# l8r.net
KiCad netlist of a schematic drawn in EAGLE
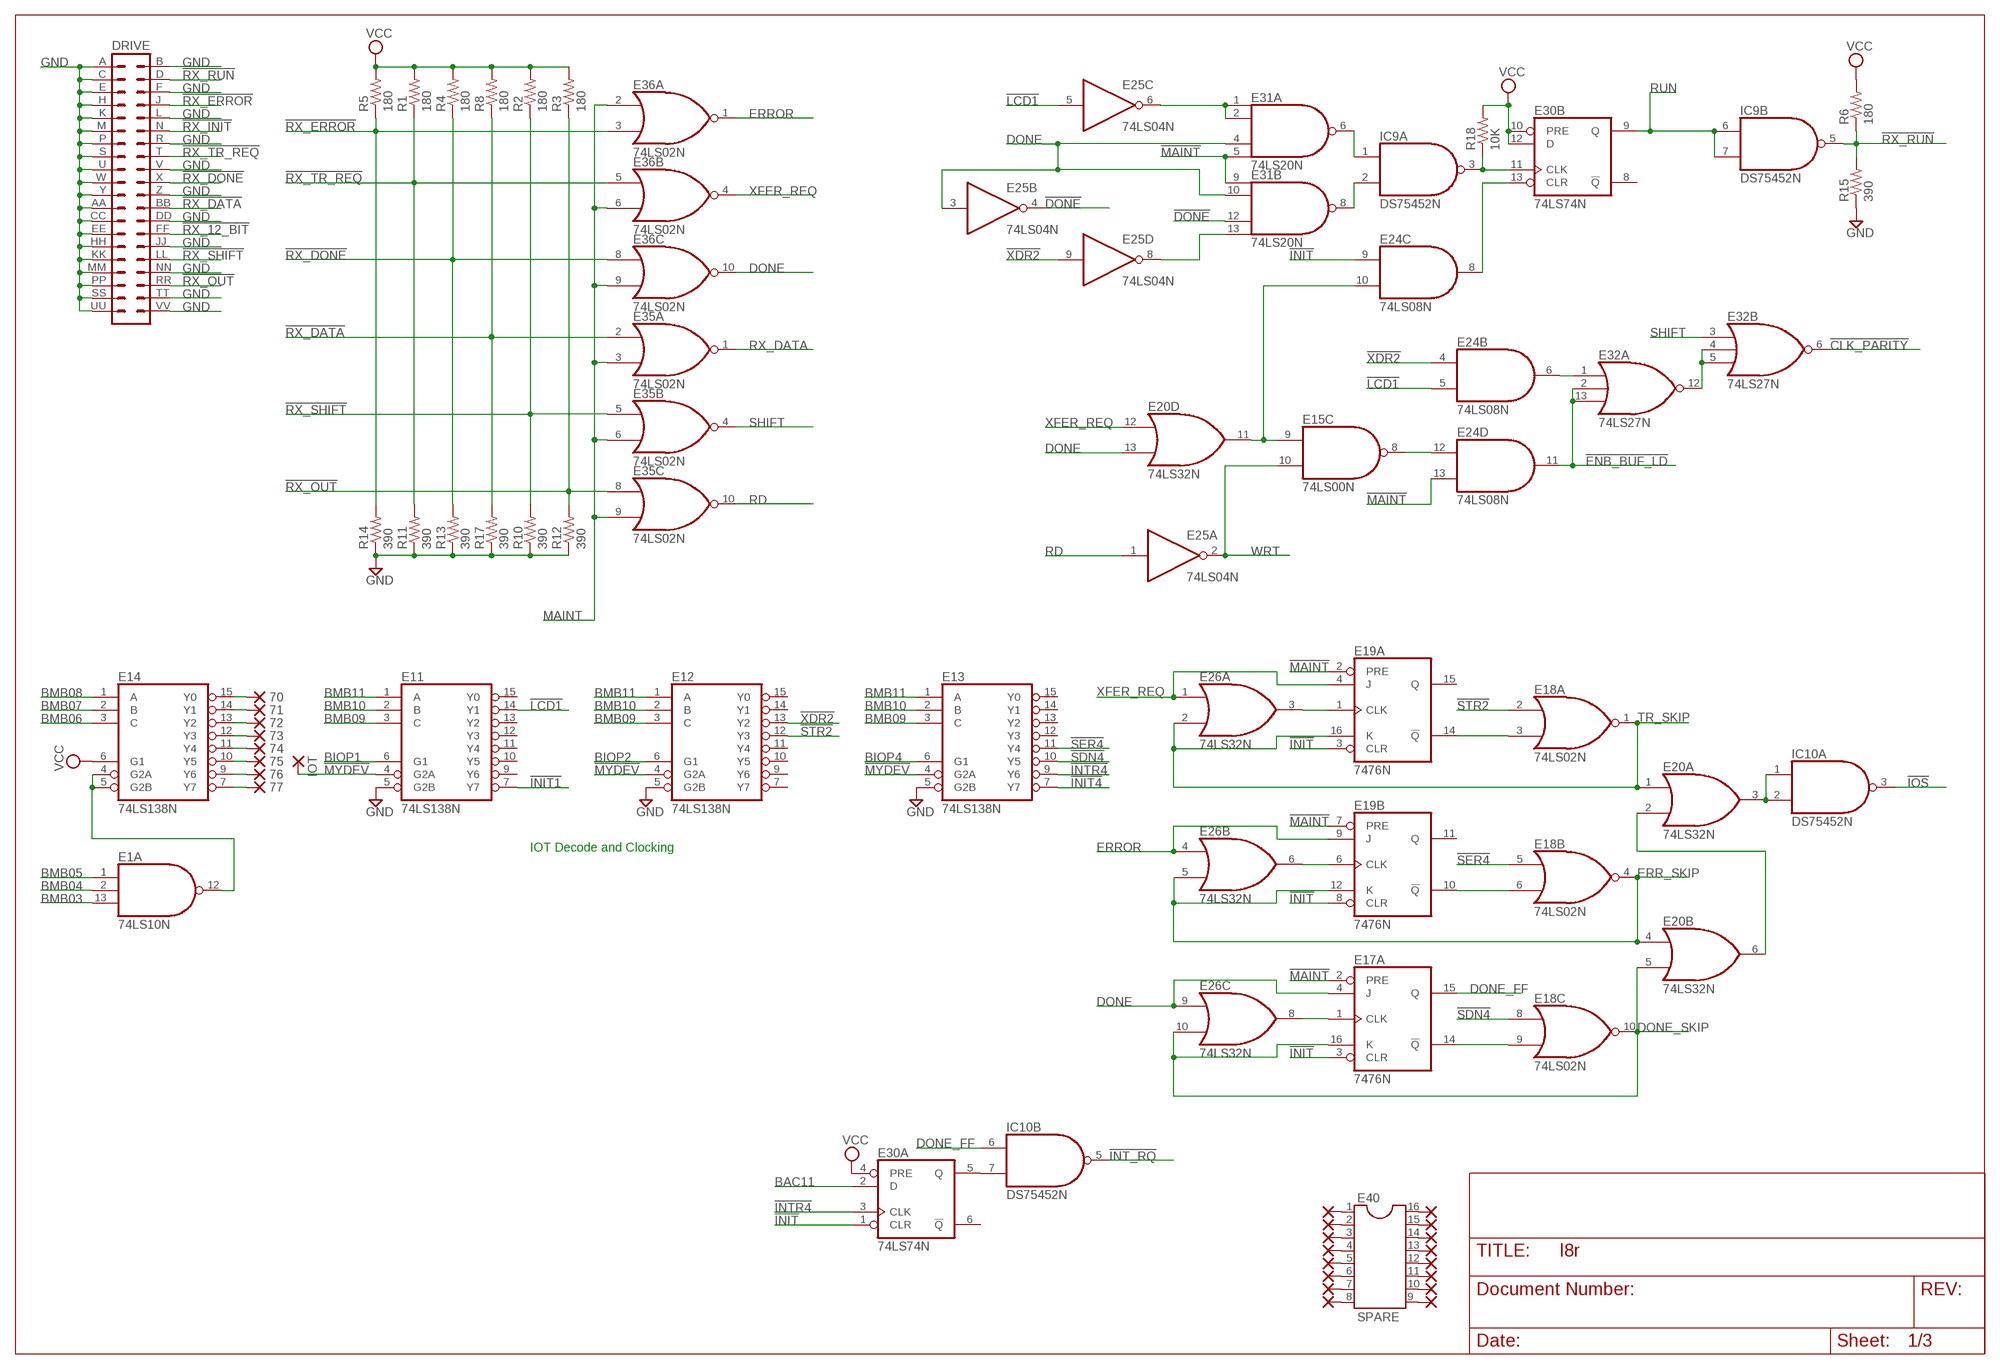
[diagram p0: schematic, sheet 1]
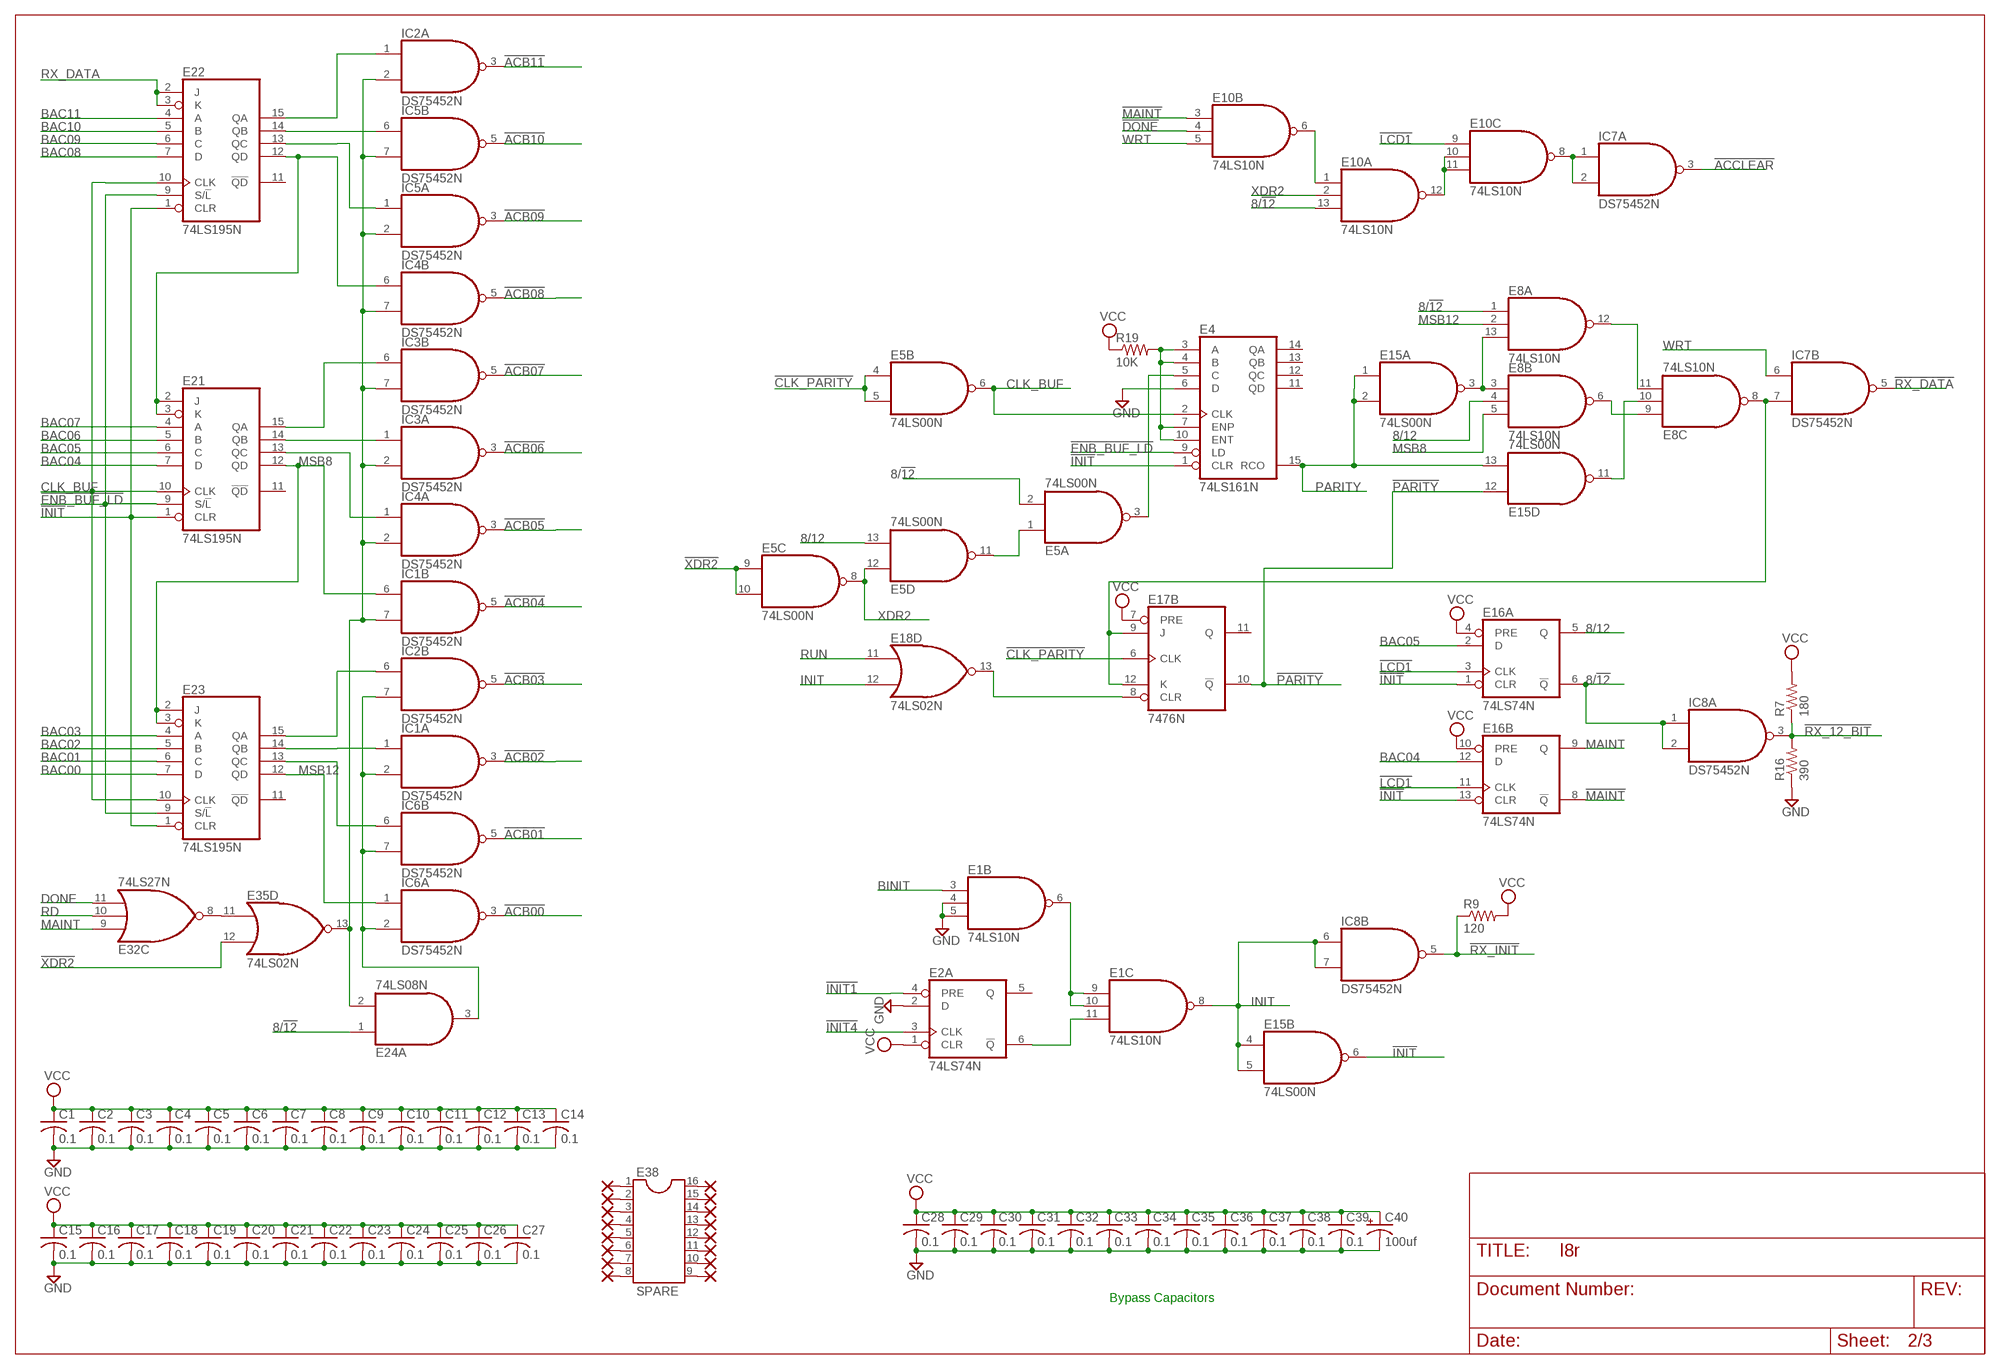
[diagram p1: schematic, sheet 2]
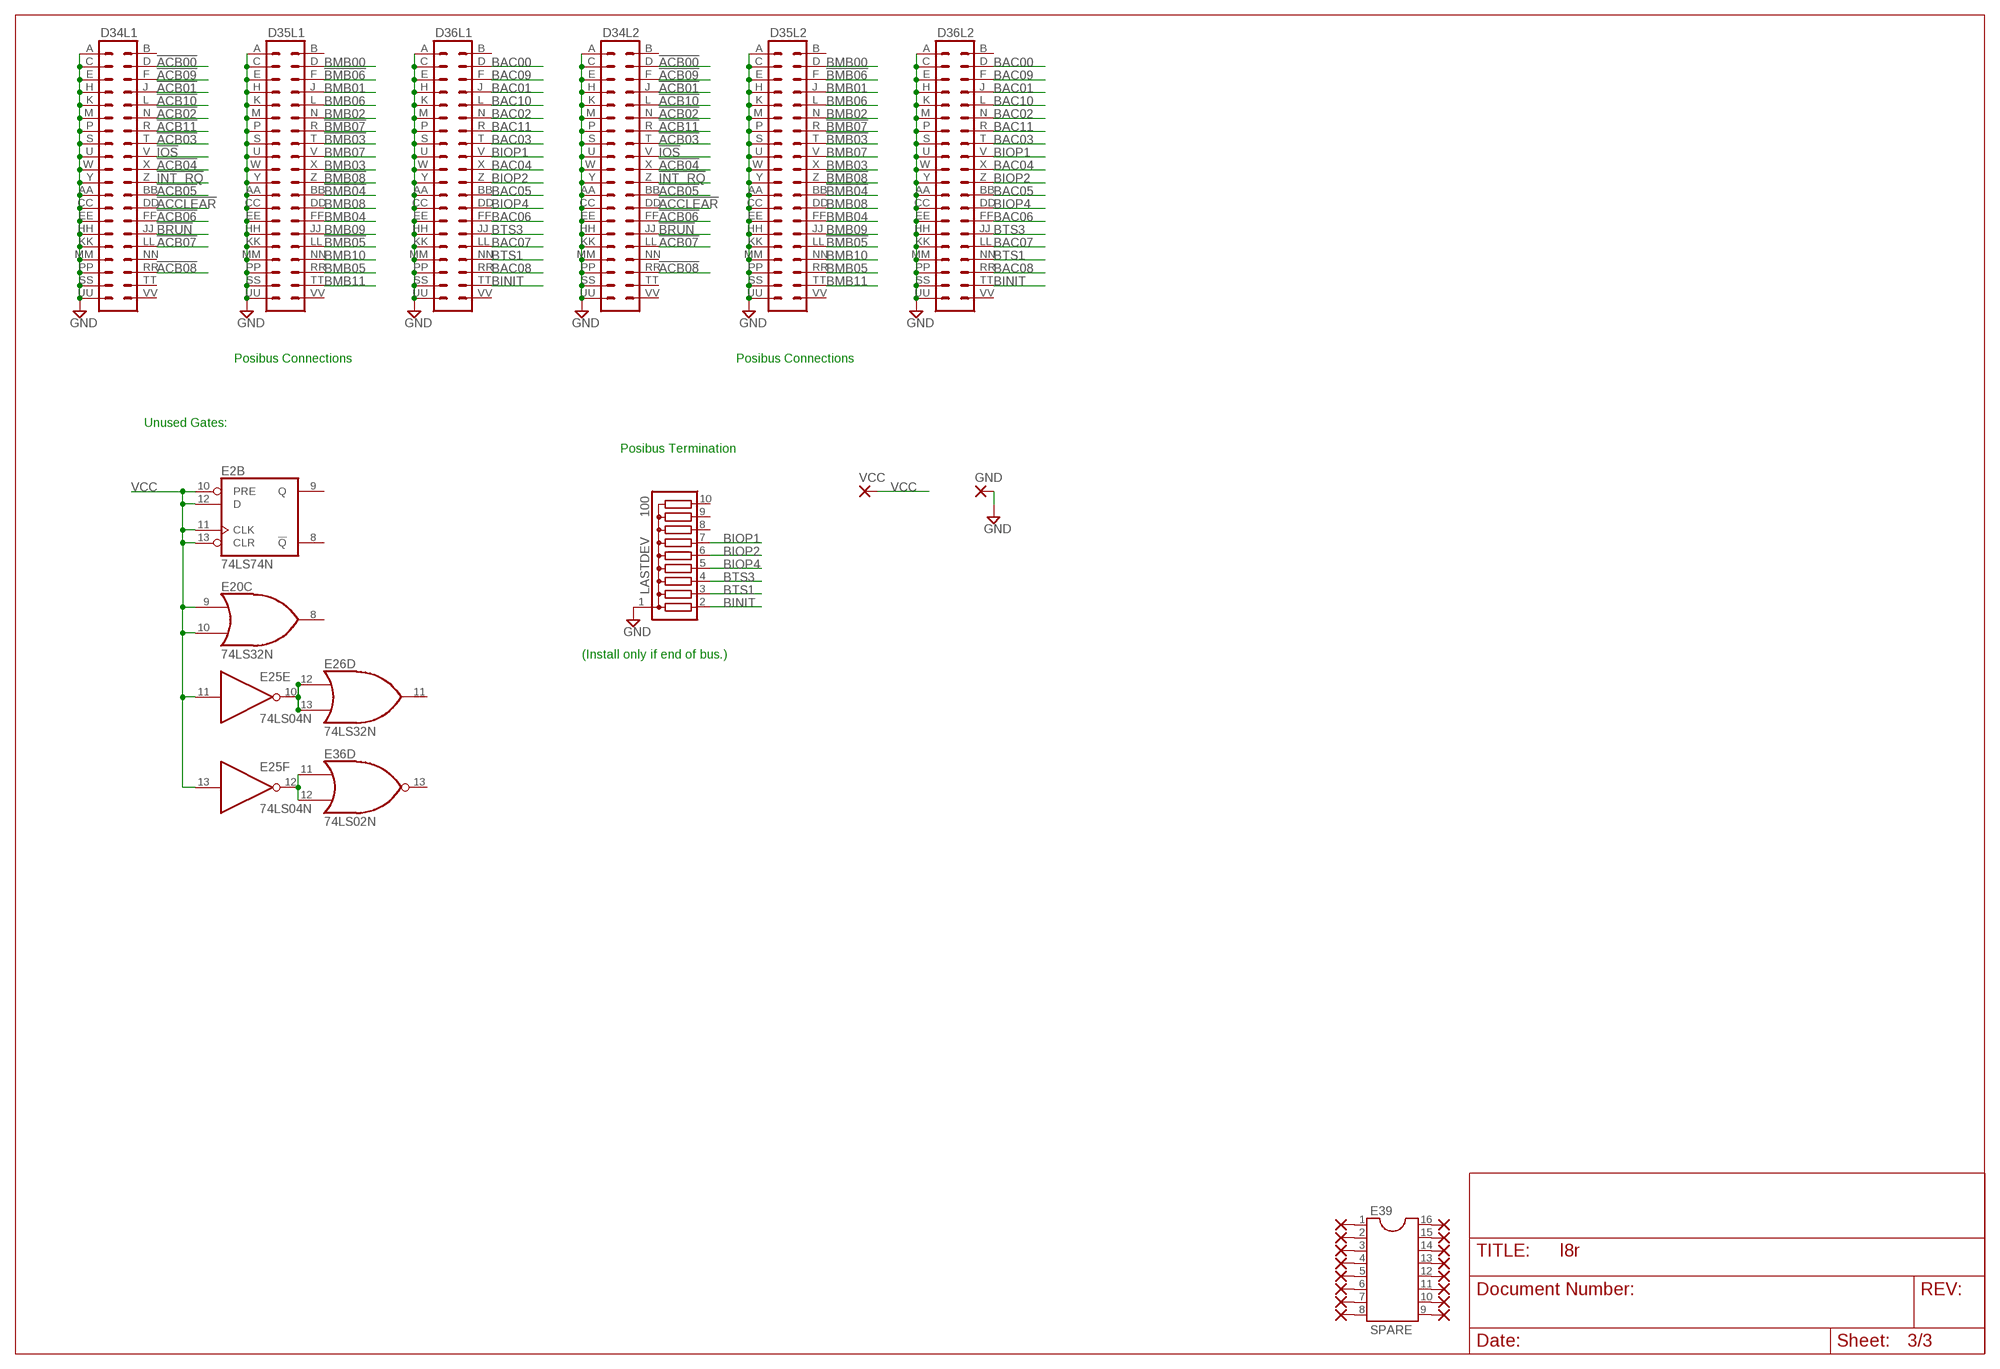
[diagram p2: schematic, sheet 3]

(export (version "E")
  (design (tool "Eeschema 10.0.6"))
  (components
    (comp (ref "D34L1")
      (value "DEC40PINV")
      (footprint "eagle-import:DEC40PINV")
      (libsource (lib "eagle-import") (part "DEC40PINV"))
    )
    (comp (ref "D34L2")
      (value "DEC40PINV")
      (footprint "eagle-import:DEC40PINV")
      (libsource (lib "eagle-import") (part "DEC40PINV"))
    )
    (comp (ref "D35L1")
      (value "DEC40PINV")
      (footprint "eagle-import:DEC40PINV")
      (libsource (lib "eagle-import") (part "DEC40PINV"))
    )
    (comp (ref "D35L2")
      (value "DEC40PINV")
      (footprint "eagle-import:DEC40PINV")
      (libsource (lib "eagle-import") (part "DEC40PINV"))
    )
    (comp (ref "D36L1")
      (value "DEC40PINV")
      (footprint "eagle-import:DEC40PINV")
      (libsource (lib "eagle-import") (part "DEC40PINV"))
    )
    (comp (ref "D36L2")
      (value "DEC40PINV")
      (footprint "eagle-import:DEC40PINV")
      (libsource (lib "eagle-import") (part "DEC40PINV"))
    )
    (comp (ref "E2")
      (value "74LS74N")
      (footprint "eagle-import:DIL14")
      (libsource (lib "eagle-import") (part "7474NLS"))
    )
    (comp (ref "E20")
      (value "74LS32N")
      (footprint "eagle-import:DIL14")
      (libsource (lib "eagle-import") (part "7432NLS"))
    )
    (comp (ref "E25")
      (value "74LS04N")
      (footprint "eagle-import:DIL14")
      (libsource (lib "eagle-import") (part "7404NLS"))
    )
    (comp (ref "E26")
      (value "74LS32N")
      (footprint "eagle-import:DIL14")
      (libsource (lib "eagle-import") (part "7432NLS"))
    )
    (comp (ref "E36")
      (value "74LS02N")
      (footprint "eagle-import:DIL14")
      (libsource (lib "eagle-import") (part "7402NLS"))
    )
    (comp (ref "E39")
      (value "SPARE")
      (footprint "eagle-import:DIL16")
      (libsource (lib "eagle-import") (part "DIL16"))
    )
    (comp (ref "GND")
      (value "2,54/0,8")
      (footprint "eagle-import:2,54_0,8")
      (libsource (lib "eagle-import") (part "2,54/0,8"))
    )
    (comp (ref "LASTDEV")
      (value "100")
      (footprint "eagle-import:SIL10")
      (libsource (lib "eagle-import") (part "G09R"))
    )
    (comp (ref "PAD42")
      (value "1,6/0,8")
      (footprint "eagle-import:1,6_0,8")
      (libsource (lib "eagle-import") (part "1,6/0,8"))
    )
    (comp (ref "PAD43")
      (value "1,6/0,8")
      (footprint "eagle-import:1,6_0,8")
      (libsource (lib "eagle-import") (part "1,6/0,8"))
    )
    (comp (ref "PAD44")
      (value "1,6/0,8")
      (footprint "eagle-import:1,6_0,8")
      (libsource (lib "eagle-import") (part "1,6/0,8"))
    )
    (comp (ref "PAD45")
      (value "1,6/0,8")
      (footprint "eagle-import:1,6_0,8")
      (libsource (lib "eagle-import") (part "1,6/0,8"))
    )
    (comp (ref "PAD46")
      (value "1,6/0,8")
      (footprint "eagle-import:1,6_0,8")
      (libsource (lib "eagle-import") (part "1,6/0,8"))
    )
    (comp (ref "PAD47")
      (value "1,6/0,8")
      (footprint "eagle-import:1,6_0,8")
      (libsource (lib "eagle-import") (part "1,6/0,8"))
    )
    (comp (ref "PAD48")
      (value "1,6/0,8")
      (footprint "eagle-import:1,6_0,8")
      (libsource (lib "eagle-import") (part "1,6/0,8"))
    )
    (comp (ref "PAD49")
      (value "1,6/0,8")
      (footprint "eagle-import:1,6_0,8")
      (libsource (lib "eagle-import") (part "1,6/0,8"))
    )
    (comp (ref "PAD50")
      (value "1,6/0,8")
      (footprint "eagle-import:1,6_0,8")
      (libsource (lib "eagle-import") (part "1,6/0,8"))
    )
    (comp (ref "PAD51")
      (value "1,6/0,8")
      (footprint "eagle-import:1,6_0,8")
      (libsource (lib "eagle-import") (part "1,6/0,8"))
    )
    (comp (ref "PAD52")
      (value "1,6/0,8")
      (footprint "eagle-import:1,6_0,8")
      (libsource (lib "eagle-import") (part "1,6/0,8"))
    )
    (comp (ref "PAD53")
      (value "1,6/0,8")
      (footprint "eagle-import:1,6_0,8")
      (libsource (lib "eagle-import") (part "1,6/0,8"))
    )
    (comp (ref "PAD54")
      (value "1,6/0,8")
      (footprint "eagle-import:1,6_0,8")
      (libsource (lib "eagle-import") (part "1,6/0,8"))
    )
    (comp (ref "PAD55")
      (value "1,6/0,8")
      (footprint "eagle-import:1,6_0,8")
      (libsource (lib "eagle-import") (part "1,6/0,8"))
    )
    (comp (ref "PAD56")
      (value "1,6/0,8")
      (footprint "eagle-import:1,6_0,8")
      (libsource (lib "eagle-import") (part "1,6/0,8"))
    )
    (comp (ref "PAD57")
      (value "1,6/0,8")
      (footprint "eagle-import:1,6_0,8")
      (libsource (lib "eagle-import") (part "1,6/0,8"))
    )
    (comp (ref "VCC")
      (value "2,54/0,8")
      (footprint "eagle-import:2,54_0,8")
      (libsource (lib "eagle-import") (part "2,54/0,8"))
    )
    (comp (ref "70")
      (value "1,6/0,8")
      (footprint "eagle-import:1,6_0,8")
      (libsource (lib "eagle-import") (part "1,6/0,8"))
    )
    (comp (ref "71")
      (value "1,6/0,8")
      (footprint "eagle-import:1,6_0,8")
      (libsource (lib "eagle-import") (part "1,6/0,8"))
    )
    (comp (ref "72")
      (value "1,6/0,8")
      (footprint "eagle-import:1,6_0,8")
      (libsource (lib "eagle-import") (part "1,6/0,8"))
    )
    (comp (ref "73")
      (value "1,6/0,8")
      (footprint "eagle-import:1,6_0,8")
      (libsource (lib "eagle-import") (part "1,6/0,8"))
    )
    (comp (ref "74")
      (value "1,6/0,8")
      (footprint "eagle-import:1,6_0,8")
      (libsource (lib "eagle-import") (part "1,6/0,8"))
    )
    (comp (ref "75")
      (value "1,6/0,8")
      (footprint "eagle-import:1,6_0,8")
      (libsource (lib "eagle-import") (part "1,6/0,8"))
    )
    (comp (ref "76")
      (value "1,6/0,8")
      (footprint "eagle-import:1,6_0,8")
      (libsource (lib "eagle-import") (part "1,6/0,8"))
    )
    (comp (ref "77")
      (value "1,6/0,8")
      (footprint "eagle-import:1,6_0,8")
      (libsource (lib "eagle-import") (part "1,6/0,8"))
    )
    (comp (ref "DRIVE")
      (value "DEC40PINV")
      (footprint "eagle-import:DEC40PINV")
      (libsource (lib "eagle-import") (part "DEC40PINV"))
    )
    (comp (ref "E1")
      (value "74LS10N")
      (footprint "eagle-import:DIL14")
      (libsource (lib "eagle-import") (part "7410NLS"))
    )
    (comp (ref "E11")
      (value "74LS138N")
      (footprint "eagle-import:DIL16")
      (libsource (lib "eagle-import") (part "74138NLS"))
    )
    (comp (ref "E12")
      (value "74LS138N")
      (footprint "eagle-import:DIL16")
      (libsource (lib "eagle-import") (part "74138NLS"))
    )
    (comp (ref "E13")
      (value "74LS138N")
      (footprint "eagle-import:DIL16")
      (libsource (lib "eagle-import") (part "74138NLS"))
    )
    (comp (ref "E14")
      (value "74LS138N")
      (footprint "eagle-import:DIL16")
      (libsource (lib "eagle-import") (part "74138NLS"))
    )
    (comp (ref "E15")
      (value "74LS00N")
      (footprint "eagle-import:DIL14")
      (libsource (lib "eagle-import") (part "7400NLS"))
    )
    (comp (ref "E17")
      (value "7476N")
      (footprint "eagle-import:DIL16")
      (libsource (lib "eagle-import") (part "7476N"))
    )
    (comp (ref "E18")
      (value "74LS02N")
      (footprint "eagle-import:DIL14")
      (libsource (lib "eagle-import") (part "7402NLS"))
    )
    (comp (ref "E19")
      (value "7476N")
      (footprint "eagle-import:DIL16")
      (libsource (lib "eagle-import") (part "7476N"))
    )
    (comp (ref "E24")
      (value "74LS08N")
      (footprint "eagle-import:DIL14")
      (libsource (lib "eagle-import") (part "7408NLS"))
    )
    (comp (ref "E30")
      (value "74LS74N")
      (footprint "eagle-import:DIL14")
      (libsource (lib "eagle-import") (part "7474NLS"))
    )
    (comp (ref "E31")
      (value "74LS20N")
      (footprint "eagle-import:DIL14")
      (libsource (lib "eagle-import") (part "7420NLS"))
    )
    (comp (ref "E32")
      (value "74LS27N")
      (footprint "eagle-import:DIL14")
      (libsource (lib "eagle-import") (part "7427NLS"))
    )
    (comp (ref "E35")
      (value "74LS02N")
      (footprint "eagle-import:DIL14")
      (libsource (lib "eagle-import") (part "7402NLS"))
    )
    (comp (ref "E40")
      (value "SPARE")
      (footprint "eagle-import:DIL16")
      (libsource (lib "eagle-import") (part "DIL16"))
    )
    (comp (ref "IC9")
      (value "DS75452N")
      (footprint "eagle-import:DIL08")
      (libsource (lib "eagle-import") (part "DS75452N"))
    )
    (comp (ref "IC10")
      (value "DS75452N")
      (footprint "eagle-import:DIL08")
      (libsource (lib "eagle-import") (part "DS75452N"))
    )
    (comp (ref "IOT")
      (value "1,6/0,8")
      (footprint "eagle-import:1,6_0,8")
      (libsource (lib "eagle-import") (part "1,6/0,8"))
    )
    (comp (ref "PAD18")
      (value "1,6/0,8")
      (footprint "eagle-import:1,6_0,8")
      (libsource (lib "eagle-import") (part "1,6/0,8"))
    )
    (comp (ref "PAD19")
      (value "1,6/0,8")
      (footprint "eagle-import:1,6_0,8")
      (libsource (lib "eagle-import") (part "1,6/0,8"))
    )
    (comp (ref "PAD28")
      (value "1,6/0,8")
      (footprint "eagle-import:1,6_0,8")
      (libsource (lib "eagle-import") (part "1,6/0,8"))
    )
    (comp (ref "PAD29")
      (value "1,6/0,8")
      (footprint "eagle-import:1,6_0,8")
      (libsource (lib "eagle-import") (part "1,6/0,8"))
    )
    (comp (ref "PAD30")
      (value "1,6/0,8")
      (footprint "eagle-import:1,6_0,8")
      (libsource (lib "eagle-import") (part "1,6/0,8"))
    )
    (comp (ref "PAD31")
      (value "1,6/0,8")
      (footprint "eagle-import:1,6_0,8")
      (libsource (lib "eagle-import") (part "1,6/0,8"))
    )
    (comp (ref "PAD32")
      (value "1,6/0,8")
      (footprint "eagle-import:1,6_0,8")
      (libsource (lib "eagle-import") (part "1,6/0,8"))
    )
    (comp (ref "PAD33")
      (value "1,6/0,8")
      (footprint "eagle-import:1,6_0,8")
      (libsource (lib "eagle-import") (part "1,6/0,8"))
    )
    (comp (ref "PAD34")
      (value "1,6/0,8")
      (footprint "eagle-import:1,6_0,8")
      (libsource (lib "eagle-import") (part "1,6/0,8"))
    )
    (comp (ref "PAD35")
      (value "1,6/0,8")
      (footprint "eagle-import:1,6_0,8")
      (libsource (lib "eagle-import") (part "1,6/0,8"))
    )
    (comp (ref "PAD36")
      (value "1,6/0,8")
      (footprint "eagle-import:1,6_0,8")
      (libsource (lib "eagle-import") (part "1,6/0,8"))
    )
    (comp (ref "PAD37")
      (value "1,6/0,8")
      (footprint "eagle-import:1,6_0,8")
      (libsource (lib "eagle-import") (part "1,6/0,8"))
    )
    (comp (ref "PAD38")
      (value "1,6/0,8")
      (footprint "eagle-import:1,6_0,8")
      (libsource (lib "eagle-import") (part "1,6/0,8"))
    )
    (comp (ref "PAD39")
      (value "1,6/0,8")
      (footprint "eagle-import:1,6_0,8")
      (libsource (lib "eagle-import") (part "1,6/0,8"))
    )
    (comp (ref "PAD40")
      (value "1,6/0,8")
      (footprint "eagle-import:1,6_0,8")
      (libsource (lib "eagle-import") (part "1,6/0,8"))
    )
    (comp (ref "PAD41")
      (value "1,6/0,8")
      (footprint "eagle-import:1,6_0,8")
      (libsource (lib "eagle-import") (part "1,6/0,8"))
    )
    (comp (ref "R1")
      (value "180")
      (footprint "eagle-import:0207_10")
      (libsource (lib "eagle-import") (part "R-US_0207/10"))
    )
    (comp (ref "R2")
      (value "180")
      (footprint "eagle-import:0207_10")
      (libsource (lib "eagle-import") (part "R-US_0207/10"))
    )
    (comp (ref "R3")
      (value "180")
      (footprint "eagle-import:0207_10")
      (libsource (lib "eagle-import") (part "R-US_0207/10"))
    )
    (comp (ref "R4")
      (value "180")
      (footprint "eagle-import:0207_10")
      (libsource (lib "eagle-import") (part "R-US_0207/10"))
    )
    (comp (ref "R5")
      (value "180")
      (footprint "eagle-import:0207_10")
      (libsource (lib "eagle-import") (part "R-US_0207/10"))
    )
    (comp (ref "R6")
      (value "180")
      (footprint "eagle-import:0207_10")
      (libsource (lib "eagle-import") (part "R-US_0207/10"))
    )
    (comp (ref "R8")
      (value "180")
      (footprint "eagle-import:0207_10")
      (libsource (lib "eagle-import") (part "R-US_0207/10"))
    )
    (comp (ref "R10")
      (value "390")
      (footprint "eagle-import:0207_10")
      (libsource (lib "eagle-import") (part "R-US_0207/10"))
    )
    (comp (ref "R11")
      (value "390")
      (footprint "eagle-import:0207_10")
      (libsource (lib "eagle-import") (part "R-US_0207/10"))
    )
    (comp (ref "R12")
      (value "390")
      (footprint "eagle-import:0207_10")
      (libsource (lib "eagle-import") (part "R-US_0207/10"))
    )
    (comp (ref "R13")
      (value "390")
      (footprint "eagle-import:0207_10")
      (libsource (lib "eagle-import") (part "R-US_0207/10"))
    )
    (comp (ref "R14")
      (value "390")
      (footprint "eagle-import:0207_10")
      (libsource (lib "eagle-import") (part "R-US_0207/10"))
    )
    (comp (ref "R15")
      (value "390")
      (footprint "eagle-import:0207_10")
      (libsource (lib "eagle-import") (part "R-US_0207/10"))
    )
    (comp (ref "R17")
      (value "390")
      (footprint "eagle-import:0207_10")
      (libsource (lib "eagle-import") (part "R-US_0207/10"))
    )
    (comp (ref "R18")
      (value "10K")
      (footprint "eagle-import:0207_10")
      (libsource (lib "eagle-import") (part "R-US_0207/10"))
    )
    (comp (ref "C1")
      (value "0.1")
      (footprint "eagle-import:C050-025X075")
      (libsource (lib "eagle-import") (part "C-US050-025X075"))
    )
    (comp (ref "C2")
      (value "0.1")
      (footprint "eagle-import:C050-025X075")
      (libsource (lib "eagle-import") (part "C-US050-025X075"))
    )
    (comp (ref "C3")
      (value "0.1")
      (footprint "eagle-import:C050-025X075")
      (libsource (lib "eagle-import") (part "C-US050-025X075"))
    )
    (comp (ref "C4")
      (value "0.1")
      (footprint "eagle-import:C050-025X075")
      (libsource (lib "eagle-import") (part "C-US050-025X075"))
    )
    (comp (ref "C5")
      (value "0.1")
      (footprint "eagle-import:C050-025X075")
      (libsource (lib "eagle-import") (part "C-US050-025X075"))
    )
    (comp (ref "C6")
      (value "0.1")
      (footprint "eagle-import:C050-025X075")
      (libsource (lib "eagle-import") (part "C-US050-025X075"))
    )
    (comp (ref "C7")
      (value "0.1")
      (footprint "eagle-import:C050-025X075")
      (libsource (lib "eagle-import") (part "C-US050-025X075"))
    )
    (comp (ref "C8")
      (value "0.1")
      (footprint "eagle-import:C050-025X075")
      (libsource (lib "eagle-import") (part "C-US050-025X075"))
    )
    (comp (ref "C9")
      (value "0.1")
      (footprint "eagle-import:C050-025X075")
      (libsource (lib "eagle-import") (part "C-US050-025X075"))
    )
    (comp (ref "C10")
      (value "0.1")
      (footprint "eagle-import:C050-025X075")
      (libsource (lib "eagle-import") (part "C-US050-025X075"))
    )
    (comp (ref "C11")
      (value "0.1")
      (footprint "eagle-import:C050-025X075")
      (libsource (lib "eagle-import") (part "C-US050-025X075"))
    )
    (comp (ref "C12")
      (value "0.1")
      (footprint "eagle-import:C050-025X075")
      (libsource (lib "eagle-import") (part "C-US050-025X075"))
    )
    (comp (ref "C13")
      (value "0.1")
      (footprint "eagle-import:C050-025X075")
      (libsource (lib "eagle-import") (part "C-US050-025X075"))
    )
    (comp (ref "C14")
      (value "0.1")
      (footprint "eagle-import:C050-025X075")
      (libsource (lib "eagle-import") (part "C-US050-025X075"))
    )
    (comp (ref "C15")
      (value "0.1")
      (footprint "eagle-import:C050-025X075")
      (libsource (lib "eagle-import") (part "C-US050-025X075"))
    )
    (comp (ref "C16")
      (value "0.1")
      (footprint "eagle-import:C050-025X075")
      (libsource (lib "eagle-import") (part "C-US050-025X075"))
    )
    (comp (ref "C17")
      (value "0.1")
      (footprint "eagle-import:C050-025X075")
      (libsource (lib "eagle-import") (part "C-US050-025X075"))
    )
    (comp (ref "C18")
      (value "0.1")
      (footprint "eagle-import:C050-025X075")
      (libsource (lib "eagle-import") (part "C-US050-025X075"))
    )
    (comp (ref "C19")
      (value "0.1")
      (footprint "eagle-import:C050-025X075")
      (libsource (lib "eagle-import") (part "C-US050-025X075"))
    )
    (comp (ref "C20")
      (value "0.1")
      (footprint "eagle-import:C050-025X075")
      (libsource (lib "eagle-import") (part "C-US050-025X075"))
    )
    (comp (ref "C21")
      (value "0.1")
      (footprint "eagle-import:C050-025X075")
      (libsource (lib "eagle-import") (part "C-US050-025X075"))
    )
    (comp (ref "C22")
      (value "0.1")
      (footprint "eagle-import:C050-025X075")
      (libsource (lib "eagle-import") (part "C-US050-025X075"))
    )
    (comp (ref "C23")
      (value "0.1")
      (footprint "eagle-import:C050-025X075")
      (libsource (lib "eagle-import") (part "C-US050-025X075"))
    )
    (comp (ref "C24")
      (value "0.1")
      (footprint "eagle-import:C050-025X075")
      (libsource (lib "eagle-import") (part "C-US050-025X075"))
    )
    (comp (ref "C25")
      (value "0.1")
      (footprint "eagle-import:C050-025X075")
      (libsource (lib "eagle-import") (part "C-US050-025X075"))
    )
    (comp (ref "C26")
      (value "0.1")
      (footprint "eagle-import:C050-025X075")
      (libsource (lib "eagle-import") (part "C-US050-025X075"))
    )
    (comp (ref "C27")
      (value "0.1")
      (footprint "eagle-import:C050-025X075")
      (libsource (lib "eagle-import") (part "C-US050-025X075"))
    )
    (comp (ref "C28")
      (value "0.1")
      (footprint "eagle-import:C050-025X075")
      (libsource (lib "eagle-import") (part "C-US050-025X075"))
    )
    (comp (ref "C29")
      (value "0.1")
      (footprint "eagle-import:C050-025X075")
      (libsource (lib "eagle-import") (part "C-US050-025X075"))
    )
    (comp (ref "C30")
      (value "0.1")
      (footprint "eagle-import:C050-025X075")
      (libsource (lib "eagle-import") (part "C-US050-025X075"))
    )
    (comp (ref "C31")
      (value "0.1")
      (footprint "eagle-import:C050-025X075")
      (libsource (lib "eagle-import") (part "C-US050-025X075"))
    )
    (comp (ref "C32")
      (value "0.1")
      (footprint "eagle-import:C050-025X075")
      (libsource (lib "eagle-import") (part "C-US050-025X075"))
    )
    (comp (ref "C33")
      (value "0.1")
      (footprint "eagle-import:C050-025X075")
      (libsource (lib "eagle-import") (part "C-US050-025X075"))
    )
    (comp (ref "C34")
      (value "0.1")
      (footprint "eagle-import:C050-025X075")
      (libsource (lib "eagle-import") (part "C-US050-025X075"))
    )
    (comp (ref "C35")
      (value "0.1")
      (footprint "eagle-import:C050-025X075")
      (libsource (lib "eagle-import") (part "C-US050-025X075"))
    )
    (comp (ref "C36")
      (value "0.1")
      (footprint "eagle-import:C050-025X075")
      (libsource (lib "eagle-import") (part "C-US050-025X075"))
    )
    (comp (ref "C37")
      (value "0.1")
      (footprint "eagle-import:C050-025X075")
      (libsource (lib "eagle-import") (part "C-US050-025X075"))
    )
    (comp (ref "C38")
      (value "0.1")
      (footprint "eagle-import:C050-025X075")
      (libsource (lib "eagle-import") (part "C-US050-025X075"))
    )
    (comp (ref "C39")
      (value "0.1")
      (footprint "eagle-import:C050-025X075")
      (libsource (lib "eagle-import") (part "C-US050-025X075"))
    )
    (comp (ref "C40")
      (value "100uf")
      (footprint "eagle-import:E22-9")
      (libsource (lib "eagle-import") (part "CPOL-USE22-9AXIAL"))
    )
    (comp (ref "E4")
      (value "74LS161N")
      (footprint "eagle-import:DIL16")
      (libsource (lib "eagle-import") (part "74161NLS"))
    )
    (comp (ref "E5")
      (value "74LS00N")
      (footprint "eagle-import:DIL14")
      (libsource (lib "eagle-import") (part "7400NLS"))
    )
    (comp (ref "E8")
      (value "74LS10N")
      (footprint "eagle-import:DIL14")
      (libsource (lib "eagle-import") (part "7410NLS"))
    )
    (comp (ref "E10")
      (value "74LS10N")
      (footprint "eagle-import:DIL14")
      (libsource (lib "eagle-import") (part "7410NLS"))
    )
    (comp (ref "E16")
      (value "74LS74N")
      (footprint "eagle-import:DIL14")
      (libsource (lib "eagle-import") (part "7474NLS"))
    )
    (comp (ref "E21")
      (value "74LS195N")
      (footprint "eagle-import:DIL16")
      (libsource (lib "eagle-import") (part "74195NLS"))
    )
    (comp (ref "E22")
      (value "74LS195N")
      (footprint "eagle-import:DIL16")
      (libsource (lib "eagle-import") (part "74195NLS"))
    )
    (comp (ref "E23")
      (value "74LS195N")
      (footprint "eagle-import:DIL16")
      (libsource (lib "eagle-import") (part "74195NLS"))
    )
    (comp (ref "E38")
      (value "SPARE")
      (footprint "eagle-import:DIL16")
      (libsource (lib "eagle-import") (part "DIL16"))
    )
    (comp (ref "IC1")
      (value "DS75452N")
      (footprint "eagle-import:DIL08")
      (libsource (lib "eagle-import") (part "DS75452N"))
    )
    (comp (ref "IC2")
      (value "DS75452N")
      (footprint "eagle-import:DIL08")
      (libsource (lib "eagle-import") (part "DS75452N"))
    )
    (comp (ref "IC3")
      (value "DS75452N")
      (footprint "eagle-import:DIL08")
      (libsource (lib "eagle-import") (part "DS75452N"))
    )
    (comp (ref "IC4")
      (value "DS75452N")
      (footprint "eagle-import:DIL08")
      (libsource (lib "eagle-import") (part "DS75452N"))
    )
    (comp (ref "IC5")
      (value "DS75452N")
      (footprint "eagle-import:DIL08")
      (libsource (lib "eagle-import") (part "DS75452N"))
    )
    (comp (ref "IC6")
      (value "DS75452N")
      (footprint "eagle-import:DIL08")
      (libsource (lib "eagle-import") (part "DS75452N"))
    )
    (comp (ref "IC7")
      (value "DS75452N")
      (footprint "eagle-import:DIL08")
      (libsource (lib "eagle-import") (part "DS75452N"))
    )
    (comp (ref "IC8")
      (value "DS75452N")
      (footprint "eagle-import:DIL08")
      (libsource (lib "eagle-import") (part "DS75452N"))
    )
    (comp (ref "PAD10")
      (value "1,6/0,8")
      (footprint "eagle-import:1,6_0,8")
      (libsource (lib "eagle-import") (part "1,6/0,8"))
    )
    (comp (ref "PAD11")
      (value "1,6/0,8")
      (footprint "eagle-import:1,6_0,8")
      (libsource (lib "eagle-import") (part "1,6/0,8"))
    )
    (comp (ref "PAD12")
      (value "1,6/0,8")
      (footprint "eagle-import:1,6_0,8")
      (libsource (lib "eagle-import") (part "1,6/0,8"))
    )
    (comp (ref "PAD13")
      (value "1,6/0,8")
      (footprint "eagle-import:1,6_0,8")
      (libsource (lib "eagle-import") (part "1,6/0,8"))
    )
    (comp (ref "PAD14")
      (value "1,6/0,8")
      (footprint "eagle-import:1,6_0,8")
      (libsource (lib "eagle-import") (part "1,6/0,8"))
    )
    (comp (ref "PAD15")
      (value "1,6/0,8")
      (footprint "eagle-import:1,6_0,8")
      (libsource (lib "eagle-import") (part "1,6/0,8"))
    )
    (comp (ref "PAD16")
      (value "1,6/0,8")
      (footprint "eagle-import:1,6_0,8")
      (libsource (lib "eagle-import") (part "1,6/0,8"))
    )
    (comp (ref "PAD17")
      (value "1,6/0,8")
      (footprint "eagle-import:1,6_0,8")
      (libsource (lib "eagle-import") (part "1,6/0,8"))
    )
    (comp (ref "PAD20")
      (value "1,6/0,8")
      (footprint "eagle-import:1,6_0,8")
      (libsource (lib "eagle-import") (part "1,6/0,8"))
    )
    (comp (ref "PAD21")
      (value "1,6/0,8")
      (footprint "eagle-import:1,6_0,8")
      (libsource (lib "eagle-import") (part "1,6/0,8"))
    )
    (comp (ref "PAD22")
      (value "1,6/0,8")
      (footprint "eagle-import:1,6_0,8")
      (libsource (lib "eagle-import") (part "1,6/0,8"))
    )
    (comp (ref "PAD23")
      (value "1,6/0,8")
      (footprint "eagle-import:1,6_0,8")
      (libsource (lib "eagle-import") (part "1,6/0,8"))
    )
    (comp (ref "PAD24")
      (value "1,6/0,8")
      (footprint "eagle-import:1,6_0,8")
      (libsource (lib "eagle-import") (part "1,6/0,8"))
    )
    (comp (ref "PAD25")
      (value "1,6/0,8")
      (footprint "eagle-import:1,6_0,8")
      (libsource (lib "eagle-import") (part "1,6/0,8"))
    )
    (comp (ref "PAD26")
      (value "1,6/0,8")
      (footprint "eagle-import:1,6_0,8")
      (libsource (lib "eagle-import") (part "1,6/0,8"))
    )
    (comp (ref "PAD27")
      (value "1,6/0,8")
      (footprint "eagle-import:1,6_0,8")
      (libsource (lib "eagle-import") (part "1,6/0,8"))
    )
    (comp (ref "R7")
      (value "180")
      (footprint "eagle-import:0207_10")
      (libsource (lib "eagle-import") (part "R-US_0207/10"))
    )
    (comp (ref "R9")
      (value "120")
      (footprint "eagle-import:0207_10")
      (libsource (lib "eagle-import") (part "R-US_0207/10"))
    )
    (comp (ref "R16")
      (value "390")
      (footprint "eagle-import:0207_10")
      (libsource (lib "eagle-import") (part "R-US_0207/10"))
    )
    (comp (ref "R19")
      (value "10K")
      (footprint "eagle-import:0207_10")
      (libsource (lib "eagle-import") (part "R-US_0207/10"))
    )
  )
  (nets
    (net (code "1") (name "8{slash}12") (class "Default")
      (node (ref "E16") (pin "5") (pinfunction "Q_5") (pintype "output"))
      (node (ref "E5") (pin "13") (pinfunction "I1_13") (pintype "input"))
      (node (ref "E8") (pin "4") (pinfunction "I1_4") (pintype "input"))
    )
    (net (code "2") (name "8{slash}~{12}") (class "Default")
      (node (ref "E10") (pin "13") (pinfunction "I2_13") (pintype "input"))
      (node (ref "E16") (pin "6") (pinfunction "~{Q}_6") (pintype "output"))
      (node (ref "E24") (pin "1") (pinfunction "I0_1") (pintype "input"))
      (node (ref "E5") (pin "2") (pinfunction "I1_2") (pintype "input"))
      (node (ref "E8") (pin "1") (pinfunction "I0_1") (pintype "input"))
      (node (ref "IC8") (pin "1") (pinfunction "I0_1") (pintype "input"))
      (node (ref "IC8") (pin "2") (pinfunction "I1_2") (pintype "input"))
    )
    (net (code "3") (name "BAC00") (class "Default")
      (node (ref "D36L1") (pin "D") (pinfunction "4_D") (pintype "bidirectional"))
      (node (ref "D36L2") (pin "D") (pinfunction "4_D") (pintype "bidirectional"))
      (node (ref "E23") (pin "7") (pinfunction "D_7") (pintype "input"))
    )
    (net (code "4") (name "BAC01") (class "Default")
      (node (ref "D36L1") (pin "J") (pinfunction "8_J") (pintype "bidirectional"))
      (node (ref "D36L2") (pin "J") (pinfunction "8_J") (pintype "bidirectional"))
      (node (ref "E23") (pin "6") (pinfunction "C_6") (pintype "input"))
    )
    (net (code "5") (name "BAC02") (class "Default")
      (node (ref "D36L1") (pin "N") (pinfunction "12_N") (pintype "bidirectional"))
      (node (ref "D36L2") (pin "N") (pinfunction "12_N") (pintype "bidirectional"))
      (node (ref "E23") (pin "5") (pinfunction "B_5") (pintype "input"))
    )
    (net (code "6") (name "BAC03") (class "Default")
      (node (ref "D36L1") (pin "T") (pinfunction "16_T") (pintype "bidirectional"))
      (node (ref "D36L2") (pin "T") (pinfunction "16_T") (pintype "bidirectional"))
      (node (ref "E23") (pin "4") (pinfunction "A_4") (pintype "input"))
    )
    (net (code "7") (name "BAC04") (class "Default")
      (node (ref "D36L1") (pin "X") (pinfunction "20_X") (pintype "bidirectional"))
      (node (ref "D36L2") (pin "X") (pinfunction "20_X") (pintype "bidirectional"))
      (node (ref "E16") (pin "12") (pinfunction "D_12") (pintype "input"))
      (node (ref "E21") (pin "7") (pinfunction "D_7") (pintype "input"))
    )
    (net (code "8") (name "BAC05") (class "Default")
      (node (ref "D36L1") (pin "BB") (pinfunction "24_BB") (pintype "bidirectional"))
      (node (ref "D36L2") (pin "BB") (pinfunction "24_BB") (pintype "bidirectional"))
      (node (ref "E16") (pin "2") (pinfunction "D_2") (pintype "input"))
      (node (ref "E21") (pin "6") (pinfunction "C_6") (pintype "input"))
    )
    (net (code "9") (name "BAC06") (class "Default")
      (node (ref "D36L1") (pin "FF") (pinfunction "28_FF") (pintype "bidirectional"))
      (node (ref "D36L2") (pin "FF") (pinfunction "28_FF") (pintype "bidirectional"))
      (node (ref "E21") (pin "5") (pinfunction "B_5") (pintype "input"))
    )
    (net (code "10") (name "BAC07") (class "Default")
      (node (ref "D36L1") (pin "LL") (pinfunction "32_LL") (pintype "bidirectional"))
      (node (ref "D36L2") (pin "LL") (pinfunction "32_LL") (pintype "bidirectional"))
      (node (ref "E21") (pin "4") (pinfunction "A_4") (pintype "input"))
    )
    (net (code "11") (name "BAC08") (class "Default")
      (node (ref "D36L1") (pin "RR") (pinfunction "36_RR") (pintype "bidirectional"))
      (node (ref "D36L2") (pin "RR") (pinfunction "36_RR") (pintype "bidirectional"))
      (node (ref "E22") (pin "7") (pinfunction "D_7") (pintype "input"))
    )
    (net (code "12") (name "BAC09") (class "Default")
      (node (ref "D36L1") (pin "F") (pinfunction "6_F") (pintype "bidirectional"))
      (node (ref "D36L2") (pin "F") (pinfunction "6_F") (pintype "bidirectional"))
      (node (ref "E22") (pin "6") (pinfunction "C_6") (pintype "input"))
    )
    (net (code "13") (name "BAC10") (class "Default")
      (node (ref "D36L1") (pin "L") (pinfunction "10_L") (pintype "bidirectional"))
      (node (ref "D36L2") (pin "L") (pinfunction "10_L") (pintype "bidirectional"))
      (node (ref "E22") (pin "5") (pinfunction "B_5") (pintype "input"))
    )
    (net (code "14") (name "BAC11") (class "Default")
      (node (ref "D36L1") (pin "R") (pinfunction "14_R") (pintype "bidirectional"))
      (node (ref "D36L2") (pin "R") (pinfunction "14_R") (pintype "bidirectional"))
      (node (ref "E22") (pin "4") (pinfunction "A_4") (pintype "input"))
      (node (ref "E30") (pin "2") (pinfunction "D_2") (pintype "input"))
    )
    (net (code "15") (name "BINIT") (class "Default")
      (node (ref "D36L1") (pin "TT") (pinfunction "38_TT") (pintype "bidirectional"))
      (node (ref "D36L2") (pin "TT") (pinfunction "38_TT") (pintype "bidirectional"))
      (node (ref "E1") (pin "3") (pinfunction "I0_3") (pintype "input"))
      (node (ref "LASTDEV") (pin "2") (pinfunction "2_2") (pintype "passive"))
    )
    (net (code "16") (name "BIOP1") (class "Default")
      (node (ref "D36L1") (pin "V") (pinfunction "18_V") (pintype "bidirectional"))
      (node (ref "D36L2") (pin "V") (pinfunction "18_V") (pintype "bidirectional"))
      (node (ref "E11") (pin "6") (pinfunction "G1_6") (pintype "input"))
      (node (ref "LASTDEV") (pin "7") (pinfunction "7_7") (pintype "passive"))
    )
    (net (code "17") (name "BIOP2") (class "Default")
      (node (ref "D36L1") (pin "Z") (pinfunction "22_Z") (pintype "bidirectional"))
      (node (ref "D36L2") (pin "Z") (pinfunction "22_Z") (pintype "bidirectional"))
      (node (ref "E12") (pin "6") (pinfunction "G1_6") (pintype "input"))
      (node (ref "LASTDEV") (pin "6") (pinfunction "6_6") (pintype "passive"))
    )
    (net (code "18") (name "BIOP4") (class "Default")
      (node (ref "D36L1") (pin "DD") (pinfunction "26_DD") (pintype "bidirectional"))
      (node (ref "D36L2") (pin "DD") (pinfunction "26_DD") (pintype "bidirectional"))
      (node (ref "E13") (pin "6") (pinfunction "G1_6") (pintype "input"))
      (node (ref "LASTDEV") (pin "5") (pinfunction "5_5") (pintype "passive"))
    )
    (net (code "19") (name "BMB00") (class "Default")
      (node (ref "D35L1") (pin "D") (pinfunction "4_D") (pintype "bidirectional"))
      (node (ref "D35L2") (pin "D") (pinfunction "4_D") (pintype "bidirectional"))
    )
    (net (code "20") (name "BMB01") (class "Default")
      (node (ref "D35L1") (pin "J") (pinfunction "8_J") (pintype "bidirectional"))
      (node (ref "D35L2") (pin "J") (pinfunction "8_J") (pintype "bidirectional"))
    )
    (net (code "21") (name "BMB02") (class "Default")
      (node (ref "D35L1") (pin "N") (pinfunction "12_N") (pintype "bidirectional"))
      (node (ref "D35L2") (pin "N") (pinfunction "12_N") (pintype "bidirectional"))
    )
    (net (code "22") (name "BMB03") (class "Default")
      (node (ref "D35L1") (pin "X") (pinfunction "20_X") (pintype "bidirectional"))
      (node (ref "D35L2") (pin "X") (pinfunction "20_X") (pintype "bidirectional"))
      (node (ref "E1") (pin "13") (pinfunction "I2_13") (pintype "input"))
    )
    (net (code "23") (name "BMB04") (class "Default")
      (node (ref "D35L1") (pin "FF") (pinfunction "28_FF") (pintype "bidirectional"))
      (node (ref "D35L2") (pin "FF") (pinfunction "28_FF") (pintype "bidirectional"))
      (node (ref "E1") (pin "2") (pinfunction "I1_2") (pintype "input"))
    )
    (net (code "24") (name "BMB05") (class "Default")
      (node (ref "D35L1") (pin "RR") (pinfunction "36_RR") (pintype "bidirectional"))
      (node (ref "D35L2") (pin "RR") (pinfunction "36_RR") (pintype "bidirectional"))
      (node (ref "E1") (pin "1") (pinfunction "I0_1") (pintype "input"))
    )
    (net (code "25") (name "BMB06") (class "Default")
      (node (ref "D35L1") (pin "L") (pinfunction "10_L") (pintype "bidirectional"))
      (node (ref "D35L2") (pin "L") (pinfunction "10_L") (pintype "bidirectional"))
      (node (ref "E14") (pin "3") (pinfunction "C_3") (pintype "input"))
    )
    (net (code "26") (name "BMB07") (class "Default")
      (node (ref "D35L1") (pin "V") (pinfunction "18_V") (pintype "bidirectional"))
      (node (ref "D35L2") (pin "V") (pinfunction "18_V") (pintype "bidirectional"))
      (node (ref "E14") (pin "2") (pinfunction "B_2") (pintype "input"))
    )
    (net (code "27") (name "BMB08") (class "Default")
      (node (ref "D35L1") (pin "DD") (pinfunction "26_DD") (pintype "bidirectional"))
      (node (ref "D35L2") (pin "DD") (pinfunction "26_DD") (pintype "bidirectional"))
      (node (ref "E14") (pin "1") (pinfunction "A_1") (pintype "input"))
    )
    (net (code "28") (name "BMB09") (class "Default")
      (node (ref "D35L1") (pin "JJ") (pinfunction "30_JJ") (pintype "bidirectional"))
      (node (ref "D35L2") (pin "JJ") (pinfunction "30_JJ") (pintype "bidirectional"))
      (node (ref "E11") (pin "3") (pinfunction "C_3") (pintype "input"))
      (node (ref "E12") (pin "3") (pinfunction "C_3") (pintype "input"))
      (node (ref "E13") (pin "3") (pinfunction "C_3") (pintype "input"))
    )
    (net (code "29") (name "BMB10") (class "Default")
      (node (ref "D35L1") (pin "NN") (pinfunction "34_NN") (pintype "bidirectional"))
      (node (ref "D35L2") (pin "NN") (pinfunction "34_NN") (pintype "bidirectional"))
      (node (ref "E11") (pin "2") (pinfunction "B_2") (pintype "input"))
      (node (ref "E12") (pin "2") (pinfunction "B_2") (pintype "input"))
      (node (ref "E13") (pin "2") (pinfunction "B_2") (pintype "input"))
    )
    (net (code "30") (name "BMB11") (class "Default")
      (node (ref "D35L1") (pin "TT") (pinfunction "38_TT") (pintype "bidirectional"))
      (node (ref "D35L2") (pin "TT") (pinfunction "38_TT") (pintype "bidirectional"))
      (node (ref "E11") (pin "1") (pinfunction "A_1") (pintype "input"))
      (node (ref "E12") (pin "1") (pinfunction "A_1") (pintype "input"))
      (node (ref "E13") (pin "1") (pinfunction "A_1") (pintype "input"))
    )
    (net (code "31") (name "BTS1") (class "Default")
      (node (ref "D36L1") (pin "NN") (pinfunction "34_NN") (pintype "bidirectional"))
      (node (ref "D36L2") (pin "NN") (pinfunction "34_NN") (pintype "bidirectional"))
      (node (ref "LASTDEV") (pin "3") (pinfunction "3_3") (pintype "passive"))
    )
    (net (code "32") (name "BTS3") (class "Default")
      (node (ref "D36L1") (pin "JJ") (pinfunction "30_JJ") (pintype "bidirectional"))
      (node (ref "D36L2") (pin "JJ") (pinfunction "30_JJ") (pintype "bidirectional"))
      (node (ref "LASTDEV") (pin "4") (pinfunction "4_4") (pintype "passive"))
    )
    (net (code "33") (name "CLK_BUF") (class "Default")
      (node (ref "E21") (pin "10") (pinfunction "CLK_10") (pintype "input"))
      (node (ref "E22") (pin "10") (pinfunction "CLK_10") (pintype "input"))
      (node (ref "E23") (pin "10") (pinfunction "CLK_10") (pintype "input"))
      (node (ref "E4") (pin "2") (pinfunction "CLK_2") (pintype "input"))
      (node (ref "E5") (pin "6") (pinfunction "O_6") (pintype "output"))
    )
    (net (code "34") (name "DONE") (class "Default")
      (node (ref "E17") (pin "4") (pinfunction "J_4") (pintype "input"))
      (node (ref "E20") (pin "13") (pinfunction "I1_13") (pintype "input"))
      (node (ref "E25") (pin "3") (pinfunction "I_3") (pintype "input"))
      (node (ref "E26") (pin "9") (pinfunction "I0_9") (pintype "input"))
      (node (ref "E31") (pin "10") (pinfunction "I1_10") (pintype "input"))
      (node (ref "E31") (pin "4") (pinfunction "I2_4") (pintype "input"))
      (node (ref "E32") (pin "11") (pinfunction "I2_11") (pintype "input"))
      (node (ref "E36") (pin "10") (pinfunction "O_10") (pintype "output"))
    )
    (net (code "35") (name "DONE_FF") (class "Default")
      (node (ref "E17") (pin "15") (pinfunction "Q_15") (pintype "output"))
      (node (ref "IC10") (pin "6") (pinfunction "I0_6") (pintype "input"))
    )
    (net (code "36") (name "DONE_SKIP") (class "Default")
      (node (ref "E17") (pin "16") (pinfunction "K_16") (pintype "input"))
      (node (ref "E18") (pin "10") (pinfunction "O_10") (pintype "output"))
      (node (ref "E20") (pin "5") (pinfunction "I1_5") (pintype "input"))
      (node (ref "E26") (pin "10") (pinfunction "I1_10") (pintype "input"))
    )
    (net (code "37") (name "ERROR") (class "Default")
      (node (ref "E19") (pin "9") (pinfunction "J_9") (pintype "input"))
      (node (ref "E26") (pin "4") (pinfunction "I0_4") (pintype "input"))
      (node (ref "E36") (pin "1") (pinfunction "O_1") (pintype "output"))
    )
    (net (code "38") (name "ERR_SKIP") (class "Default")
      (node (ref "E18") (pin "4") (pinfunction "O_4") (pintype "output"))
      (node (ref "E19") (pin "12") (pinfunction "K_12") (pintype "input"))
      (node (ref "E20") (pin "4") (pinfunction "I0_4") (pintype "input"))
      (node (ref "E26") (pin "5") (pinfunction "I1_5") (pintype "input"))
    )
    (net (code "39") (name "GND") (class "Default")
      (node (ref "C1") (pin "2") (pinfunction "2_2") (pintype "passive"))
      (node (ref "C10") (pin "2") (pinfunction "2_2") (pintype "passive"))
      (node (ref "C11") (pin "2") (pinfunction "2_2") (pintype "passive"))
      (node (ref "C12") (pin "2") (pinfunction "2_2") (pintype "passive"))
      (node (ref "C13") (pin "2") (pinfunction "2_2") (pintype "passive"))
      (node (ref "C14") (pin "2") (pinfunction "2_2") (pintype "passive"))
      (node (ref "C15") (pin "2") (pinfunction "2_2") (pintype "passive"))
      (node (ref "C16") (pin "2") (pinfunction "2_2") (pintype "passive"))
      (node (ref "C17") (pin "2") (pinfunction "2_2") (pintype "passive"))
      (node (ref "C18") (pin "2") (pinfunction "2_2") (pintype "passive"))
      (node (ref "C19") (pin "2") (pinfunction "2_2") (pintype "passive"))
      (node (ref "C2") (pin "2") (pinfunction "2_2") (pintype "passive"))
      (node (ref "C20") (pin "2") (pinfunction "2_2") (pintype "passive"))
      (node (ref "C21") (pin "2") (pinfunction "2_2") (pintype "passive"))
      (node (ref "C22") (pin "2") (pinfunction "2_2") (pintype "passive"))
      (node (ref "C23") (pin "2") (pinfunction "2_2") (pintype "passive"))
      (node (ref "C24") (pin "2") (pinfunction "2_2") (pintype "passive"))
      (node (ref "C25") (pin "2") (pinfunction "2_2") (pintype "passive"))
      (node (ref "C26") (pin "2") (pinfunction "2_2") (pintype "passive"))
      (node (ref "C27") (pin "2") (pinfunction "2_2") (pintype "passive"))
      (node (ref "C28") (pin "2") (pinfunction "2_2") (pintype "passive"))
      (node (ref "C29") (pin "2") (pinfunction "2_2") (pintype "passive"))
      (node (ref "C3") (pin "2") (pinfunction "2_2") (pintype "passive"))
      (node (ref "C30") (pin "2") (pinfunction "2_2") (pintype "passive"))
      (node (ref "C31") (pin "2") (pinfunction "2_2") (pintype "passive"))
      (node (ref "C32") (pin "2") (pinfunction "2_2") (pintype "passive"))
      (node (ref "C33") (pin "2") (pinfunction "2_2") (pintype "passive"))
      (node (ref "C34") (pin "2") (pinfunction "2_2") (pintype "passive"))
      (node (ref "C35") (pin "2") (pinfunction "2_2") (pintype "passive"))
      (node (ref "C36") (pin "2") (pinfunction "2_2") (pintype "passive"))
      (node (ref "C37") (pin "2") (pinfunction "2_2") (pintype "passive"))
      (node (ref "C38") (pin "2") (pinfunction "2_2") (pintype "passive"))
      (node (ref "C39") (pin "2") (pinfunction "2_2") (pintype "passive"))
      (node (ref "C4") (pin "2") (pinfunction "2_2") (pintype "passive"))
      (node (ref "C40") (pin "-") (pinfunction "-_-") (pintype "passive"))
      (node (ref "C5") (pin "2") (pinfunction "2_2") (pintype "passive"))
      (node (ref "C6") (pin "2") (pinfunction "2_2") (pintype "passive"))
      (node (ref "C7") (pin "2") (pinfunction "2_2") (pintype "passive"))
      (node (ref "C8") (pin "2") (pinfunction "2_2") (pintype "passive"))
      (node (ref "C9") (pin "2") (pinfunction "2_2") (pintype "passive"))
      (node (ref "D34L1") (pin "A") (pinfunction "1_A") (pintype "bidirectional"))
      (node (ref "D34L1") (pin "AA") (pinfunction "23_AA") (pintype "bidirectional"))
      (node (ref "D34L1") (pin "C") (pinfunction "3_C") (pintype "bidirectional"))
      (node (ref "D34L1") (pin "CC") (pinfunction "25_CC") (pintype "bidirectional"))
      (node (ref "D34L1") (pin "E") (pinfunction "5_E") (pintype "bidirectional"))
      (node (ref "D34L1") (pin "EE") (pinfunction "27_EE") (pintype "bidirectional"))
      (node (ref "D34L1") (pin "H") (pinfunction "7_H") (pintype "bidirectional"))
      (node (ref "D34L1") (pin "HH") (pinfunction "29_HH") (pintype "bidirectional"))
      (node (ref "D34L1") (pin "K") (pinfunction "9_K") (pintype "bidirectional"))
      (node (ref "D34L1") (pin "KK") (pinfunction "31_KK") (pintype "bidirectional"))
      (node (ref "D34L1") (pin "M") (pinfunction "11_M") (pintype "bidirectional"))
      (node (ref "D34L1") (pin "MM") (pinfunction "33_MM") (pintype "bidirectional"))
      (node (ref "D34L1") (pin "P") (pinfunction "13_P") (pintype "bidirectional"))
      (node (ref "D34L1") (pin "PP") (pinfunction "35_PP") (pintype "bidirectional"))
      (node (ref "D34L1") (pin "S") (pinfunction "15_S") (pintype "bidirectional"))
      (node (ref "D34L1") (pin "SS") (pinfunction "37_SS") (pintype "bidirectional"))
      (node (ref "D34L1") (pin "U") (pinfunction "17_U") (pintype "bidirectional"))
      (node (ref "D34L1") (pin "UU") (pinfunction "39_UU") (pintype "bidirectional"))
      (node (ref "D34L1") (pin "W") (pinfunction "19_W") (pintype "bidirectional"))
      (node (ref "D34L1") (pin "Y") (pinfunction "21_Y") (pintype "bidirectional"))
      (node (ref "D34L2") (pin "A") (pinfunction "1_A") (pintype "bidirectional"))
      (node (ref "D34L2") (pin "AA") (pinfunction "23_AA") (pintype "bidirectional"))
      (node (ref "D34L2") (pin "C") (pinfunction "3_C") (pintype "bidirectional"))
      (node (ref "D34L2") (pin "CC") (pinfunction "25_CC") (pintype "bidirectional"))
      (node (ref "D34L2") (pin "E") (pinfunction "5_E") (pintype "bidirectional"))
      (node (ref "D34L2") (pin "EE") (pinfunction "27_EE") (pintype "bidirectional"))
      (node (ref "D34L2") (pin "H") (pinfunction "7_H") (pintype "bidirectional"))
      (node (ref "D34L2") (pin "HH") (pinfunction "29_HH") (pintype "bidirectional"))
      (node (ref "D34L2") (pin "K") (pinfunction "9_K") (pintype "bidirectional"))
      (node (ref "D34L2") (pin "KK") (pinfunction "31_KK") (pintype "bidirectional"))
      (node (ref "D34L2") (pin "M") (pinfunction "11_M") (pintype "bidirectional"))
      (node (ref "D34L2") (pin "MM") (pinfunction "33_MM") (pintype "bidirectional"))
      (node (ref "D34L2") (pin "P") (pinfunction "13_P") (pintype "bidirectional"))
      (node (ref "D34L2") (pin "PP") (pinfunction "35_PP") (pintype "bidirectional"))
      (node (ref "D34L2") (pin "S") (pinfunction "15_S") (pintype "bidirectional"))
      (node (ref "D34L2") (pin "SS") (pinfunction "37_SS") (pintype "bidirectional"))
      (node (ref "D34L2") (pin "U") (pinfunction "17_U") (pintype "bidirectional"))
      (node (ref "D34L2") (pin "UU") (pinfunction "39_UU") (pintype "bidirectional"))
      (node (ref "D34L2") (pin "W") (pinfunction "19_W") (pintype "bidirectional"))
      (node (ref "D34L2") (pin "Y") (pinfunction "21_Y") (pintype "bidirectional"))
      (node (ref "D35L1") (pin "A") (pinfunction "1_A") (pintype "bidirectional"))
      (node (ref "D35L1") (pin "AA") (pinfunction "23_AA") (pintype "bidirectional"))
      (node (ref "D35L1") (pin "C") (pinfunction "3_C") (pintype "bidirectional"))
      (node (ref "D35L1") (pin "CC") (pinfunction "25_CC") (pintype "bidirectional"))
      (node (ref "D35L1") (pin "E") (pinfunction "5_E") (pintype "bidirectional"))
      (node (ref "D35L1") (pin "EE") (pinfunction "27_EE") (pintype "bidirectional"))
      (node (ref "D35L1") (pin "H") (pinfunction "7_H") (pintype "bidirectional"))
      (node (ref "D35L1") (pin "HH") (pinfunction "29_HH") (pintype "bidirectional"))
      (node (ref "D35L1") (pin "K") (pinfunction "9_K") (pintype "bidirectional"))
      (node (ref "D35L1") (pin "KK") (pinfunction "31_KK") (pintype "bidirectional"))
      (node (ref "D35L1") (pin "M") (pinfunction "11_M") (pintype "bidirectional"))
      (node (ref "D35L1") (pin "MM") (pinfunction "33_MM") (pintype "bidirectional"))
      (node (ref "D35L1") (pin "P") (pinfunction "13_P") (pintype "bidirectional"))
      (node (ref "D35L1") (pin "PP") (pinfunction "35_PP") (pintype "bidirectional"))
      (node (ref "D35L1") (pin "S") (pinfunction "15_S") (pintype "bidirectional"))
      (node (ref "D35L1") (pin "SS") (pinfunction "37_SS") (pintype "bidirectional"))
      (node (ref "D35L1") (pin "U") (pinfunction "17_U") (pintype "bidirectional"))
      (node (ref "D35L1") (pin "UU") (pinfunction "39_UU") (pintype "bidirectional"))
      (node (ref "D35L1") (pin "W") (pinfunction "19_W") (pintype "bidirectional"))
      (node (ref "D35L1") (pin "Y") (pinfunction "21_Y") (pintype "bidirectional"))
      (node (ref "D35L2") (pin "A") (pinfunction "1_A") (pintype "bidirectional"))
      (node (ref "D35L2") (pin "AA") (pinfunction "23_AA") (pintype "bidirectional"))
      (node (ref "D35L2") (pin "C") (pinfunction "3_C") (pintype "bidirectional"))
      (node (ref "D35L2") (pin "CC") (pinfunction "25_CC") (pintype "bidirectional"))
      (node (ref "D35L2") (pin "E") (pinfunction "5_E") (pintype "bidirectional"))
      (node (ref "D35L2") (pin "EE") (pinfunction "27_EE") (pintype "bidirectional"))
      (node (ref "D35L2") (pin "H") (pinfunction "7_H") (pintype "bidirectional"))
      (node (ref "D35L2") (pin "HH") (pinfunction "29_HH") (pintype "bidirectional"))
      (node (ref "D35L2") (pin "K") (pinfunction "9_K") (pintype "bidirectional"))
      (node (ref "D35L2") (pin "KK") (pinfunction "31_KK") (pintype "bidirectional"))
      (node (ref "D35L2") (pin "M") (pinfunction "11_M") (pintype "bidirectional"))
      (node (ref "D35L2") (pin "MM") (pinfunction "33_MM") (pintype "bidirectional"))
      (node (ref "D35L2") (pin "P") (pinfunction "13_P") (pintype "bidirectional"))
      (node (ref "D35L2") (pin "PP") (pinfunction "35_PP") (pintype "bidirectional"))
      (node (ref "D35L2") (pin "S") (pinfunction "15_S") (pintype "bidirectional"))
      (node (ref "D35L2") (pin "SS") (pinfunction "37_SS") (pintype "bidirectional"))
      (node (ref "D35L2") (pin "U") (pinfunction "17_U") (pintype "bidirectional"))
      (node (ref "D35L2") (pin "UU") (pinfunction "39_UU") (pintype "bidirectional"))
      (node (ref "D35L2") (pin "W") (pinfunction "19_W") (pintype "bidirectional"))
      (node (ref "D35L2") (pin "Y") (pinfunction "21_Y") (pintype "bidirectional"))
      (node (ref "D36L1") (pin "A") (pinfunction "1_A") (pintype "bidirectional"))
      (node (ref "D36L1") (pin "AA") (pinfunction "23_AA") (pintype "bidirectional"))
      (node (ref "D36L1") (pin "C") (pinfunction "3_C") (pintype "bidirectional"))
      (node (ref "D36L1") (pin "CC") (pinfunction "25_CC") (pintype "bidirectional"))
      (node (ref "D36L1") (pin "E") (pinfunction "5_E") (pintype "bidirectional"))
      (node (ref "D36L1") (pin "EE") (pinfunction "27_EE") (pintype "bidirectional"))
      (node (ref "D36L1") (pin "H") (pinfunction "7_H") (pintype "bidirectional"))
      (node (ref "D36L1") (pin "HH") (pinfunction "29_HH") (pintype "bidirectional"))
      (node (ref "D36L1") (pin "K") (pinfunction "9_K") (pintype "bidirectional"))
      (node (ref "D36L1") (pin "KK") (pinfunction "31_KK") (pintype "bidirectional"))
      (node (ref "D36L1") (pin "M") (pinfunction "11_M") (pintype "bidirectional"))
      (node (ref "D36L1") (pin "MM") (pinfunction "33_MM") (pintype "bidirectional"))
      (node (ref "D36L1") (pin "P") (pinfunction "13_P") (pintype "bidirectional"))
      (node (ref "D36L1") (pin "PP") (pinfunction "35_PP") (pintype "bidirectional"))
      (node (ref "D36L1") (pin "S") (pinfunction "15_S") (pintype "bidirectional"))
      (node (ref "D36L1") (pin "SS") (pinfunction "37_SS") (pintype "bidirectional"))
      (node (ref "D36L1") (pin "U") (pinfunction "17_U") (pintype "bidirectional"))
      (node (ref "D36L1") (pin "UU") (pinfunction "39_UU") (pintype "bidirectional"))
      (node (ref "D36L1") (pin "W") (pinfunction "19_W") (pintype "bidirectional"))
      (node (ref "D36L1") (pin "Y") (pinfunction "21_Y") (pintype "bidirectional"))
      (node (ref "D36L2") (pin "A") (pinfunction "1_A") (pintype "bidirectional"))
      (node (ref "D36L2") (pin "AA") (pinfunction "23_AA") (pintype "bidirectional"))
      (node (ref "D36L2") (pin "C") (pinfunction "3_C") (pintype "bidirectional"))
      (node (ref "D36L2") (pin "CC") (pinfunction "25_CC") (pintype "bidirectional"))
      (node (ref "D36L2") (pin "E") (pinfunction "5_E") (pintype "bidirectional"))
      (node (ref "D36L2") (pin "EE") (pinfunction "27_EE") (pintype "bidirectional"))
      (node (ref "D36L2") (pin "H") (pinfunction "7_H") (pintype "bidirectional"))
      (node (ref "D36L2") (pin "HH") (pinfunction "29_HH") (pintype "bidirectional"))
      (node (ref "D36L2") (pin "K") (pinfunction "9_K") (pintype "bidirectional"))
      (node (ref "D36L2") (pin "KK") (pinfunction "31_KK") (pintype "bidirectional"))
      (node (ref "D36L2") (pin "M") (pinfunction "11_M") (pintype "bidirectional"))
      (node (ref "D36L2") (pin "MM") (pinfunction "33_MM") (pintype "bidirectional"))
      (node (ref "D36L2") (pin "P") (pinfunction "13_P") (pintype "bidirectional"))
      (node (ref "D36L2") (pin "PP") (pinfunction "35_PP") (pintype "bidirectional"))
      (node (ref "D36L2") (pin "S") (pinfunction "15_S") (pintype "bidirectional"))
      (node (ref "D36L2") (pin "SS") (pinfunction "37_SS") (pintype "bidirectional"))
      (node (ref "D36L2") (pin "U") (pinfunction "17_U") (pintype "bidirectional"))
      (node (ref "D36L2") (pin "UU") (pinfunction "39_UU") (pintype "bidirectional"))
      (node (ref "D36L2") (pin "W") (pinfunction "19_W") (pintype "bidirectional"))
      (node (ref "D36L2") (pin "Y") (pinfunction "21_Y") (pintype "bidirectional"))
      (node (ref "DRIVE") (pin "A") (pinfunction "1_A") (pintype "bidirectional"))
      (node (ref "DRIVE") (pin "AA") (pinfunction "23_AA") (pintype "bidirectional"))
      (node (ref "DRIVE") (pin "B") (pinfunction "2_B") (pintype "bidirectional"))
      (node (ref "DRIVE") (pin "C") (pinfunction "3_C") (pintype "bidirectional"))
      (node (ref "DRIVE") (pin "CC") (pinfunction "25_CC") (pintype "bidirectional"))
      (node (ref "DRIVE") (pin "DD") (pinfunction "26_DD") (pintype "bidirectional"))
      (node (ref "DRIVE") (pin "E") (pinfunction "5_E") (pintype "bidirectional"))
      (node (ref "DRIVE") (pin "EE") (pinfunction "27_EE") (pintype "bidirectional"))
      (node (ref "DRIVE") (pin "F") (pinfunction "6_F") (pintype "bidirectional"))
      (node (ref "DRIVE") (pin "H") (pinfunction "7_H") (pintype "bidirectional"))
      (node (ref "DRIVE") (pin "HH") (pinfunction "29_HH") (pintype "bidirectional"))
      (node (ref "DRIVE") (pin "JJ") (pinfunction "30_JJ") (pintype "bidirectional"))
      (node (ref "DRIVE") (pin "K") (pinfunction "9_K") (pintype "bidirectional"))
      (node (ref "DRIVE") (pin "KK") (pinfunction "31_KK") (pintype "bidirectional"))
      (node (ref "DRIVE") (pin "L") (pinfunction "10_L") (pintype "bidirectional"))
      (node (ref "DRIVE") (pin "M") (pinfunction "11_M") (pintype "bidirectional"))
      (node (ref "DRIVE") (pin "MM") (pinfunction "33_MM") (pintype "bidirectional"))
      (node (ref "DRIVE") (pin "NN") (pinfunction "34_NN") (pintype "bidirectional"))
      (node (ref "DRIVE") (pin "P") (pinfunction "13_P") (pintype "bidirectional"))
      (node (ref "DRIVE") (pin "PP") (pinfunction "35_PP") (pintype "bidirectional"))
      (node (ref "DRIVE") (pin "R") (pinfunction "14_R") (pintype "bidirectional"))
      (node (ref "DRIVE") (pin "S") (pinfunction "15_S") (pintype "bidirectional"))
      (node (ref "DRIVE") (pin "SS") (pinfunction "37_SS") (pintype "bidirectional"))
      (node (ref "DRIVE") (pin "TT") (pinfunction "38_TT") (pintype "bidirectional"))
      (node (ref "DRIVE") (pin "U") (pinfunction "17_U") (pintype "bidirectional"))
      (node (ref "DRIVE") (pin "UU") (pinfunction "39_UU") (pintype "bidirectional"))
      (node (ref "DRIVE") (pin "V") (pinfunction "18_V") (pintype "bidirectional"))
      (node (ref "DRIVE") (pin "VV") (pinfunction "40_VV") (pintype "bidirectional"))
      (node (ref "DRIVE") (pin "W") (pinfunction "19_W") (pintype "bidirectional"))
      (node (ref "DRIVE") (pin "Y") (pinfunction "21_Y") (pintype "bidirectional"))
      (node (ref "DRIVE") (pin "Z") (pinfunction "22_Z") (pintype "bidirectional"))
      (node (ref "E1") (pin "4") (pinfunction "I1_4") (pintype "input"))
      (node (ref "E1") (pin "5") (pinfunction "I2_5") (pintype "input"))
      (node (ref "E11") (pin "5") (pinfunction "G2B_5") (pintype "input"))
      (node (ref "E12") (pin "5") (pinfunction "G2B_5") (pintype "input"))
      (node (ref "E13") (pin "5") (pinfunction "G2B_5") (pintype "input"))
      (node (ref "E2") (pin "2") (pinfunction "D_2") (pintype "input"))
      (node (ref "E4") (pin "6") (pinfunction "D_6") (pintype "input"))
      (node (ref "GND") (pin "1") (pinfunction "P_1") (pintype "passive"))
      (node (ref "LASTDEV") (pin "1") (pinfunction "1_1") (pintype "passive"))
      (node (ref "R10") (pin "1") (pinfunction "1_1") (pintype "passive"))
      (node (ref "R11") (pin "1") (pinfunction "1_1") (pintype "passive"))
      (node (ref "R12") (pin "1") (pinfunction "1_1") (pintype "passive"))
      (node (ref "R13") (pin "1") (pinfunction "1_1") (pintype "passive"))
      (node (ref "R14") (pin "1") (pinfunction "1_1") (pintype "passive"))
      (node (ref "R15") (pin "1") (pinfunction "1_1") (pintype "passive"))
      (node (ref "R16") (pin "1") (pinfunction "1_1") (pintype "passive"))
      (node (ref "R17") (pin "1") (pinfunction "1_1") (pintype "passive"))
    )
    (net (code "40") (name "INIT") (class "Default")
      (node (ref "E1") (pin "8") (pinfunction "O_8") (pintype "output"))
      (node (ref "E15") (pin "4") (pinfunction "I0_4") (pintype "input"))
      (node (ref "E15") (pin "5") (pinfunction "I1_5") (pintype "input"))
      (node (ref "E18") (pin "12") (pinfunction "I1_12") (pintype "input"))
      (node (ref "IC8") (pin "6") (pinfunction "I0_6") (pintype "input"))
      (node (ref "IC8") (pin "7") (pinfunction "I1_7") (pintype "input"))
    )
    (net (code "41") (name "MAINT") (class "Default")
      (node (ref "E16") (pin "9") (pinfunction "Q_9") (pintype "output"))
      (node (ref "E32") (pin "9") (pinfunction "I0_9") (pintype "input"))
      (node (ref "E35") (pin "3") (pinfunction "I1_3") (pintype "input"))
      (node (ref "E35") (pin "6") (pinfunction "I1_6") (pintype "input"))
      (node (ref "E35") (pin "9") (pinfunction "I1_9") (pintype "input"))
      (node (ref "E36") (pin "2") (pinfunction "I0_2") (pintype "input"))
      (node (ref "E36") (pin "6") (pinfunction "I1_6") (pintype "input"))
      (node (ref "E36") (pin "9") (pinfunction "I1_9") (pintype "input"))
    )
    (net (code "42") (name "MSB8") (class "Default")
      (node (ref "E21") (pin "12") (pinfunction "QD_12") (pintype "output"))
      (node (ref "E23") (pin "2") (pinfunction "J_2") (pintype "input"))
      (node (ref "E23") (pin "3") (pinfunction "K_3") (pintype "input"))
      (node (ref "E8") (pin "5") (pinfunction "I2_5") (pintype "input"))
      (node (ref "IC1") (pin "6") (pinfunction "I0_6") (pintype "input"))
    )
    (net (code "43") (name "MSB12") (class "Default")
      (node (ref "E23") (pin "12") (pinfunction "QD_12") (pintype "output"))
      (node (ref "E8") (pin "2") (pinfunction "I1_2") (pintype "input"))
      (node (ref "IC6") (pin "1") (pinfunction "I0_1") (pintype "input"))
    )
    (net (code "44") (name "Net-(70-P)") (class "Default")
      (node (ref "70") (pin "1") (pinfunction "P_1") (pintype "passive"))
      (node (ref "E14") (pin "15") (pinfunction "Y0_15") (pintype "output"))
    )
    (net (code "45") (name "Net-(71-P)") (class "Default")
      (node (ref "71") (pin "1") (pinfunction "P_1") (pintype "passive"))
      (node (ref "E14") (pin "14") (pinfunction "Y1_14") (pintype "output"))
    )
    (net (code "46") (name "Net-(72-P)") (class "Default")
      (node (ref "72") (pin "1") (pinfunction "P_1") (pintype "passive"))
      (node (ref "E14") (pin "13") (pinfunction "Y2_13") (pintype "output"))
    )
    (net (code "47") (name "Net-(73-P)") (class "Default")
      (node (ref "73") (pin "1") (pinfunction "P_1") (pintype "passive"))
      (node (ref "E14") (pin "12") (pinfunction "Y3_12") (pintype "output"))
    )
    (net (code "48") (name "Net-(74-P)") (class "Default")
      (node (ref "74") (pin "1") (pinfunction "P_1") (pintype "passive"))
      (node (ref "E14") (pin "11") (pinfunction "Y4_11") (pintype "output"))
    )
    (net (code "49") (name "Net-(75-P)") (class "Default")
      (node (ref "75") (pin "1") (pinfunction "P_1") (pintype "passive"))
      (node (ref "E14") (pin "10") (pinfunction "Y5_10") (pintype "output"))
    )
    (net (code "50") (name "Net-(76-P)") (class "Default")
      (node (ref "76") (pin "1") (pinfunction "P_1") (pintype "passive"))
      (node (ref "E14") (pin "9") (pinfunction "Y6_9") (pintype "output"))
    )
    (net (code "51") (name "Net-(77-P)") (class "Default")
      (node (ref "77") (pin "1") (pinfunction "P_1") (pintype "passive"))
      (node (ref "E14") (pin "7") (pinfunction "Y7_7") (pintype "output"))
    )
    (net (code "52") (name "Net-(E1B-O)") (class "Default")
      (node (ref "E1") (pin "10") (pinfunction "I1_10") (pintype "input"))
      (node (ref "E1") (pin "6") (pinfunction "O_6") (pintype "output"))
      (node (ref "E1") (pin "9") (pinfunction "I0_9") (pintype "input"))
    )
    (net (code "53") (name "Net-(E1C-I2)") (class "Default")
      (node (ref "E1") (pin "11") (pinfunction "I2_11") (pintype "input"))
      (node (ref "E2") (pin "6") (pinfunction "~{Q}_6") (pintype "output"))
    )
    (net (code "54") (name "Net-(E4A-A)") (class "Default")
      (node (ref "E4") (pin "10") (pinfunction "ENT_10") (pintype "input"))
      (node (ref "E4") (pin "3") (pinfunction "A_3") (pintype "input"))
      (node (ref "E4") (pin "4") (pinfunction "B_4") (pintype "input"))
      (node (ref "E4") (pin "7") (pinfunction "ENP_7") (pintype "input"))
      (node (ref "R19") (pin "2") (pinfunction "2_2") (pintype "passive"))
    )
    (net (code "55") (name "Net-(E4A-C)") (class "Default")
      (node (ref "E4") (pin "5") (pinfunction "C_5") (pintype "input"))
      (node (ref "E5") (pin "3") (pinfunction "O_3") (pintype "output"))
    )
    (net (code "56") (name "Net-(E5A-I0)") (class "Default")
      (node (ref "E5") (pin "1") (pinfunction "I0_1") (pintype "input"))
      (node (ref "E5") (pin "11") (pinfunction "O_11") (pintype "output"))
    )
    (net (code "57") (name "Net-(E8A-O)") (class "Default")
      (node (ref "E8") (pin "11") (pinfunction "I2_11") (pintype "input"))
      (node (ref "E8") (pin "12") (pinfunction "O_12") (pintype "output"))
    )
    (net (code "58") (name "Net-(E8B-O)") (class "Default")
      (node (ref "E8") (pin "6") (pinfunction "O_6") (pintype "output"))
      (node (ref "E8") (pin "9") (pinfunction "I0_9") (pintype "input"))
    )
    (net (code "59") (name "Net-(E10A-I0)") (class "Default")
      (node (ref "E10") (pin "1") (pinfunction "I0_1") (pintype "input"))
      (node (ref "E10") (pin "6") (pinfunction "O_6") (pintype "output"))
    )
    (net (code "60") (name "Net-(E10A-O)") (class "Default")
      (node (ref "E10") (pin "10") (pinfunction "I1_10") (pintype "input"))
      (node (ref "E10") (pin "11") (pinfunction "I2_11") (pintype "input"))
      (node (ref "E10") (pin "12") (pinfunction "O_12") (pintype "output"))
    )
    (net (code "61") (name "Net-(E10C-O)") (class "Default")
      (node (ref "E10") (pin "8") (pinfunction "O_8") (pintype "output"))
      (node (ref "IC7") (pin "1") (pinfunction "I0_1") (pintype "input"))
      (node (ref "IC7") (pin "2") (pinfunction "I1_2") (pintype "input"))
    )
    (net (code "62") (name "Net-(E14A-G2A)") (class "Default")
      (node (ref "E1") (pin "12") (pinfunction "O_12") (pintype "output"))
      (node (ref "E14") (pin "4") (pinfunction "G2A_4") (pintype "input"))
      (node (ref "E14") (pin "5") (pinfunction "G2B_5") (pintype "input"))
    )
    (net (code "63") (name "Net-(E15A-O)") (class "Default")
      (node (ref "E15") (pin "3") (pinfunction "O_3") (pintype "output"))
      (node (ref "E8") (pin "13") (pinfunction "I2_13") (pintype "input"))
      (node (ref "E8") (pin "3") (pinfunction "I0_3") (pintype "input"))
    )
    (net (code "64") (name "Net-(E15C-I0)") (class "Default")
      (node (ref "E15") (pin "9") (pinfunction "I0_9") (pintype "input"))
      (node (ref "E20") (pin "11") (pinfunction "O_11") (pintype "output"))
      (node (ref "E24") (pin "10") (pinfunction "I1_10") (pintype "input"))
    )
    (net (code "65") (name "Net-(E15C-O)") (class "Default")
      (node (ref "E15") (pin "8") (pinfunction "O_8") (pintype "output"))
      (node (ref "E24") (pin "12") (pinfunction "I0_12") (pintype "input"))
    )
    (net (code "66") (name "Net-(E15D-O)") (class "Default")
      (node (ref "E15") (pin "11") (pinfunction "O_11") (pintype "output"))
      (node (ref "E8") (pin "10") (pinfunction "I1_10") (pintype "input"))
    )
    (net (code "67") (name "Net-(E17A-CLK)") (class "Default")
      (node (ref "E17") (pin "1") (pinfunction "CLK_1") (pintype "input"))
      (node (ref "E26") (pin "8") (pinfunction "O_8") (pintype "output"))
    )
    (net (code "68") (name "Net-(E17A-~{Q})") (class "Default")
      (node (ref "E17") (pin "14") (pinfunction "~{Q}_14") (pintype "output"))
      (node (ref "E18") (pin "9") (pinfunction "I1_9") (pintype "input"))
    )
    (net (code "69") (name "Net-(E17B-CLR)") (class "Default")
      (node (ref "E17") (pin "8") (pinfunction "CLR_8") (pintype "input"))
      (node (ref "E18") (pin "13") (pinfunction "O_13") (pintype "output"))
    )
    (net (code "70") (name "Net-(E17B-J)") (class "Default")
      (node (ref "E17") (pin "12") (pinfunction "K_12") (pintype "input"))
      (node (ref "E17") (pin "9") (pinfunction "J_9") (pintype "input"))
      (node (ref "E8") (pin "8") (pinfunction "O_8") (pintype "output"))
      (node (ref "IC7") (pin "7") (pinfunction "I1_7") (pintype "input"))
    )
    (net (code "71") (name "Net-(E18A-I1)") (class "Default")
      (node (ref "E18") (pin "3") (pinfunction "I1_3") (pintype "input"))
      (node (ref "E19") (pin "14") (pinfunction "~{Q}_14") (pintype "output"))
    )
    (net (code "72") (name "Net-(E18B-I1)") (class "Default")
      (node (ref "E18") (pin "6") (pinfunction "I1_6") (pintype "input"))
      (node (ref "E19") (pin "10") (pinfunction "~{Q}_10") (pintype "output"))
    )
    (net (code "73") (name "Net-(E19A-CLK)") (class "Default")
      (node (ref "E19") (pin "1") (pinfunction "CLK_1") (pintype "input"))
      (node (ref "E26") (pin "3") (pinfunction "O_3") (pintype "output"))
    )
    (net (code "74") (name "Net-(E19B-CLK)") (class "Default")
      (node (ref "E19") (pin "6") (pinfunction "CLK_6") (pintype "input"))
      (node (ref "E26") (pin "6") (pinfunction "O_6") (pintype "output"))
    )
    (net (code "75") (name "Net-(E20A-I1)") (class "Default")
      (node (ref "E20") (pin "2") (pinfunction "I1_2") (pintype "input"))
      (node (ref "E20") (pin "6") (pinfunction "O_6") (pintype "output"))
    )
    (net (code "76") (name "Net-(E20A-O)") (class "Default")
      (node (ref "E20") (pin "3") (pinfunction "O_3") (pintype "output"))
      (node (ref "IC10") (pin "1") (pinfunction "I0_1") (pintype "input"))
      (node (ref "IC10") (pin "2") (pinfunction "I1_2") (pintype "input"))
    )
    (net (code "77") (name "Net-(E21A-J)") (class "Default")
      (node (ref "E21") (pin "2") (pinfunction "J_2") (pintype "input"))
      (node (ref "E21") (pin "3") (pinfunction "K_3") (pintype "input"))
      (node (ref "E22") (pin "12") (pinfunction "QD_12") (pintype "output"))
      (node (ref "IC4") (pin "6") (pinfunction "I0_6") (pintype "input"))
    )
    (net (code "78") (name "Net-(E21A-QA)") (class "Default")
      (node (ref "E21") (pin "15") (pinfunction "QA_15") (pintype "output"))
      (node (ref "IC3") (pin "6") (pinfunction "I0_6") (pintype "input"))
    )
    (net (code "79") (name "Net-(E21A-QB)") (class "Default")
      (node (ref "E21") (pin "14") (pinfunction "QB_14") (pintype "output"))
      (node (ref "IC3") (pin "1") (pinfunction "I0_1") (pintype "input"))
    )
    (net (code "80") (name "Net-(E21A-QC)") (class "Default")
      (node (ref "E21") (pin "13") (pinfunction "QC_13") (pintype "output"))
      (node (ref "IC4") (pin "1") (pinfunction "I0_1") (pintype "input"))
    )
    (net (code "81") (name "Net-(E22A-QA)") (class "Default")
      (node (ref "E22") (pin "15") (pinfunction "QA_15") (pintype "output"))
      (node (ref "IC2") (pin "1") (pinfunction "I0_1") (pintype "input"))
    )
    (net (code "82") (name "Net-(E22A-QB)") (class "Default")
      (node (ref "E22") (pin "14") (pinfunction "QB_14") (pintype "output"))
      (node (ref "IC5") (pin "6") (pinfunction "I0_6") (pintype "input"))
    )
    (net (code "83") (name "Net-(E22A-QC)") (class "Default")
      (node (ref "E22") (pin "13") (pinfunction "QC_13") (pintype "output"))
      (node (ref "IC5") (pin "1") (pinfunction "I0_1") (pintype "input"))
    )
    (net (code "84") (name "Net-(E23A-QA)") (class "Default")
      (node (ref "E23") (pin "15") (pinfunction "QA_15") (pintype "output"))
      (node (ref "IC2") (pin "6") (pinfunction "I0_6") (pintype "input"))
    )
    (net (code "85") (name "Net-(E23A-QB)") (class "Default")
      (node (ref "E23") (pin "14") (pinfunction "QB_14") (pintype "output"))
      (node (ref "IC1") (pin "1") (pinfunction "I0_1") (pintype "input"))
    )
    (net (code "86") (name "Net-(E23A-QC)") (class "Default")
      (node (ref "E23") (pin "13") (pinfunction "QC_13") (pintype "output"))
      (node (ref "IC6") (pin "6") (pinfunction "I0_6") (pintype "input"))
    )
    (net (code "87") (name "Net-(E24A-I1)") (class "Default")
      (node (ref "E24") (pin "2") (pinfunction "I1_2") (pintype "input"))
      (node (ref "E35") (pin "13") (pinfunction "O_13") (pintype "output"))
      (node (ref "IC1") (pin "7") (pinfunction "I1_7") (pintype "input"))
      (node (ref "IC2") (pin "2") (pinfunction "I1_2") (pintype "input"))
      (node (ref "IC3") (pin "2") (pinfunction "I1_2") (pintype "input"))
      (node (ref "IC3") (pin "7") (pinfunction "I1_7") (pintype "input"))
      (node (ref "IC4") (pin "2") (pinfunction "I1_2") (pintype "input"))
      (node (ref "IC4") (pin "7") (pinfunction "I1_7") (pintype "input"))
      (node (ref "IC5") (pin "2") (pinfunction "I1_2") (pintype "input"))
      (node (ref "IC5") (pin "7") (pinfunction "I1_7") (pintype "input"))
    )
    (net (code "88") (name "Net-(E24A-O)") (class "Default")
      (node (ref "E24") (pin "3") (pinfunction "O_3") (pintype "output"))
      (node (ref "IC1") (pin "2") (pinfunction "I1_2") (pintype "input"))
      (node (ref "IC2") (pin "7") (pinfunction "I1_7") (pintype "input"))
      (node (ref "IC6") (pin "2") (pinfunction "I1_2") (pintype "input"))
      (node (ref "IC6") (pin "7") (pinfunction "I1_7") (pintype "input"))
    )
    (net (code "89") (name "Net-(E24B-O)") (class "Default")
      (node (ref "E24") (pin "6") (pinfunction "O_6") (pintype "output"))
      (node (ref "E32") (pin "1") (pinfunction "I0_1") (pintype "input"))
    )
    (net (code "90") (name "Net-(E24C-O)") (class "Default")
      (node (ref "E24") (pin "8") (pinfunction "O_8") (pintype "output"))
      (node (ref "E30") (pin "13") (pinfunction "CLR_13") (pintype "input"))
    )
    (net (code "91") (name "Net-(E25C-O)") (class "Default")
      (node (ref "E25") (pin "6") (pinfunction "O_6") (pintype "output"))
      (node (ref "E31") (pin "1") (pinfunction "I0_1") (pintype "input"))
      (node (ref "E31") (pin "2") (pinfunction "I1_2") (pintype "input"))
    )
    (net (code "92") (name "Net-(E25D-O)") (class "Default")
      (node (ref "E25") (pin "8") (pinfunction "O_8") (pintype "output"))
      (node (ref "E31") (pin "13") (pinfunction "I3_13") (pintype "input"))
    )
    (net (code "93") (name "Net-(E25E-O)") (class "Default")
      (node (ref "E25") (pin "10") (pinfunction "O_10") (pintype "output"))
      (node (ref "E26") (pin "12") (pinfunction "I0_12") (pintype "input"))
      (node (ref "E26") (pin "13") (pinfunction "I1_13") (pintype "input"))
    )
    (net (code "94") (name "Net-(E25F-O)") (class "Default")
      (node (ref "E25") (pin "12") (pinfunction "O_12") (pintype "output"))
      (node (ref "E36") (pin "11") (pinfunction "I0_11") (pintype "input"))
      (node (ref "E36") (pin "12") (pinfunction "I1_12") (pintype "input"))
    )
    (net (code "95") (name "Net-(E30A-Q)") (class "Default")
      (node (ref "E30") (pin "5") (pinfunction "Q_5") (pintype "output"))
      (node (ref "IC10") (pin "7") (pinfunction "I1_7") (pintype "input"))
    )
    (net (code "96") (name "Net-(E30B-CLK)") (class "Default")
      (node (ref "E30") (pin "11") (pinfunction "CLK_11") (pintype "input"))
      (node (ref "IC9") (pin "3") (pinfunction "O_3") (pintype "open_collector"))
      (node (ref "R18") (pin "1") (pinfunction "1_1") (pintype "passive"))
    )
    (net (code "97") (name "Net-(E31A-O)") (class "Default")
      (node (ref "E31") (pin "6") (pinfunction "O_6") (pintype "output"))
      (node (ref "IC9") (pin "1") (pinfunction "I0_1") (pintype "input"))
    )
    (net (code "98") (name "Net-(E31B-O)") (class "Default")
      (node (ref "E31") (pin "8") (pinfunction "O_8") (pintype "output"))
      (node (ref "IC9") (pin "2") (pinfunction "I1_2") (pintype "input"))
    )
    (net (code "99") (name "Net-(E32A-O)") (class "Default")
      (node (ref "E32") (pin "12") (pinfunction "O_12") (pintype "output"))
      (node (ref "E32") (pin "4") (pinfunction "I1_4") (pintype "input"))
      (node (ref "E32") (pin "5") (pinfunction "I2_5") (pintype "input"))
    )
    (net (code "100") (name "Net-(E32C-O)") (class "Default")
      (node (ref "E32") (pin "8") (pinfunction "O_8") (pintype "output"))
      (node (ref "E35") (pin "11") (pinfunction "I0_11") (pintype "input"))
    )
    (net (code "101") (name "Net-(PAD10-P)") (class "Default")
      (node (ref "E38") (pin "1") (pinfunction "1_1") (pintype "passive"))
      (node (ref "PAD10") (pin "1") (pinfunction "P_1") (pintype "passive"))
    )
    (net (code "102") (name "Net-(PAD11-P)") (class "Default")
      (node (ref "E38") (pin "2") (pinfunction "2_2") (pintype "passive"))
      (node (ref "PAD11") (pin "1") (pinfunction "P_1") (pintype "passive"))
    )
    (net (code "103") (name "Net-(PAD12-P)") (class "Default")
      (node (ref "E38") (pin "3") (pinfunction "3_3") (pintype "passive"))
      (node (ref "PAD12") (pin "1") (pinfunction "P_1") (pintype "passive"))
    )
    (net (code "104") (name "Net-(PAD13-P)") (class "Default")
      (node (ref "E38") (pin "4") (pinfunction "4_4") (pintype "passive"))
      (node (ref "PAD13") (pin "1") (pinfunction "P_1") (pintype "passive"))
    )
    (net (code "105") (name "Net-(PAD14-P)") (class "Default")
      (node (ref "E38") (pin "5") (pinfunction "5_5") (pintype "passive"))
      (node (ref "PAD14") (pin "1") (pinfunction "P_1") (pintype "passive"))
    )
    (net (code "106") (name "Net-(PAD15-P)") (class "Default")
      (node (ref "E38") (pin "6") (pinfunction "6_6") (pintype "passive"))
      (node (ref "PAD15") (pin "1") (pinfunction "P_1") (pintype "passive"))
    )
    (net (code "107") (name "Net-(PAD16-P)") (class "Default")
      (node (ref "E38") (pin "7") (pinfunction "7_7") (pintype "passive"))
      (node (ref "PAD16") (pin "1") (pinfunction "P_1") (pintype "passive"))
    )
    (net (code "108") (name "Net-(PAD17-P)") (class "Default")
      (node (ref "E38") (pin "8") (pinfunction "8_8") (pintype "passive"))
      (node (ref "PAD17") (pin "1") (pinfunction "P_1") (pintype "passive"))
    )
    (net (code "109") (name "Net-(PAD18-P)") (class "Default")
      (node (ref "E40") (pin "1") (pinfunction "1_1") (pintype "passive"))
      (node (ref "PAD18") (pin "1") (pinfunction "P_1") (pintype "passive"))
    )
    (net (code "110") (name "Net-(PAD19-P)") (class "Default")
      (node (ref "E40") (pin "2") (pinfunction "2_2") (pintype "passive"))
      (node (ref "PAD19") (pin "1") (pinfunction "P_1") (pintype "passive"))
    )
    (net (code "111") (name "Net-(PAD20-P)") (class "Default")
      (node (ref "E38") (pin "16") (pinfunction "16_16") (pintype "passive"))
      (node (ref "PAD20") (pin "1") (pinfunction "P_1") (pintype "passive"))
    )
    (net (code "112") (name "Net-(PAD21-P)") (class "Default")
      (node (ref "E38") (pin "15") (pinfunction "15_15") (pintype "passive"))
      (node (ref "PAD21") (pin "1") (pinfunction "P_1") (pintype "passive"))
    )
    (net (code "113") (name "Net-(PAD22-P)") (class "Default")
      (node (ref "E38") (pin "14") (pinfunction "14_14") (pintype "passive"))
      (node (ref "PAD22") (pin "1") (pinfunction "P_1") (pintype "passive"))
    )
    (net (code "114") (name "Net-(PAD23-P)") (class "Default")
      (node (ref "E38") (pin "13") (pinfunction "13_13") (pintype "passive"))
      (node (ref "PAD23") (pin "1") (pinfunction "P_1") (pintype "passive"))
    )
    (net (code "115") (name "Net-(PAD24-P)") (class "Default")
      (node (ref "E38") (pin "12") (pinfunction "12_12") (pintype "passive"))
      (node (ref "PAD24") (pin "1") (pinfunction "P_1") (pintype "passive"))
    )
    (net (code "116") (name "Net-(PAD25-P)") (class "Default")
      (node (ref "E38") (pin "11") (pinfunction "11_11") (pintype "passive"))
      (node (ref "PAD25") (pin "1") (pinfunction "P_1") (pintype "passive"))
    )
    (net (code "117") (name "Net-(PAD26-P)") (class "Default")
      (node (ref "E38") (pin "10") (pinfunction "10_10") (pintype "passive"))
      (node (ref "PAD26") (pin "1") (pinfunction "P_1") (pintype "passive"))
    )
    (net (code "118") (name "Net-(PAD27-P)") (class "Default")
      (node (ref "E38") (pin "9") (pinfunction "9_9") (pintype "passive"))
      (node (ref "PAD27") (pin "1") (pinfunction "P_1") (pintype "passive"))
    )
    (net (code "119") (name "Net-(PAD28-P)") (class "Default")
      (node (ref "E40") (pin "3") (pinfunction "3_3") (pintype "passive"))
      (node (ref "PAD28") (pin "1") (pinfunction "P_1") (pintype "passive"))
    )
    (net (code "120") (name "Net-(PAD29-P)") (class "Default")
      (node (ref "E40") (pin "4") (pinfunction "4_4") (pintype "passive"))
      (node (ref "PAD29") (pin "1") (pinfunction "P_1") (pintype "passive"))
    )
    (net (code "121") (name "Net-(PAD30-P)") (class "Default")
      (node (ref "E40") (pin "5") (pinfunction "5_5") (pintype "passive"))
      (node (ref "PAD30") (pin "1") (pinfunction "P_1") (pintype "passive"))
    )
    (net (code "122") (name "Net-(PAD31-P)") (class "Default")
      (node (ref "E40") (pin "6") (pinfunction "6_6") (pintype "passive"))
      (node (ref "PAD31") (pin "1") (pinfunction "P_1") (pintype "passive"))
    )
    (net (code "123") (name "Net-(PAD32-P)") (class "Default")
      (node (ref "E40") (pin "7") (pinfunction "7_7") (pintype "passive"))
      (node (ref "PAD32") (pin "1") (pinfunction "P_1") (pintype "passive"))
    )
    (net (code "124") (name "Net-(PAD33-P)") (class "Default")
      (node (ref "E40") (pin "8") (pinfunction "8_8") (pintype "passive"))
      (node (ref "PAD33") (pin "1") (pinfunction "P_1") (pintype "passive"))
    )
    (net (code "125") (name "Net-(PAD34-P)") (class "Default")
      (node (ref "E40") (pin "16") (pinfunction "16_16") (pintype "passive"))
      (node (ref "PAD34") (pin "1") (pinfunction "P_1") (pintype "passive"))
    )
    (net (code "126") (name "Net-(PAD35-P)") (class "Default")
      (node (ref "E40") (pin "15") (pinfunction "15_15") (pintype "passive"))
      (node (ref "PAD35") (pin "1") (pinfunction "P_1") (pintype "passive"))
    )
    (net (code "127") (name "Net-(PAD36-P)") (class "Default")
      (node (ref "E40") (pin "14") (pinfunction "14_14") (pintype "passive"))
      (node (ref "PAD36") (pin "1") (pinfunction "P_1") (pintype "passive"))
    )
    (net (code "128") (name "Net-(PAD37-P)") (class "Default")
      (node (ref "E40") (pin "13") (pinfunction "13_13") (pintype "passive"))
      (node (ref "PAD37") (pin "1") (pinfunction "P_1") (pintype "passive"))
    )
    (net (code "129") (name "Net-(PAD38-P)") (class "Default")
      (node (ref "E40") (pin "12") (pinfunction "12_12") (pintype "passive"))
      (node (ref "PAD38") (pin "1") (pinfunction "P_1") (pintype "passive"))
    )
    (net (code "130") (name "Net-(PAD39-P)") (class "Default")
      (node (ref "E40") (pin "11") (pinfunction "11_11") (pintype "passive"))
      (node (ref "PAD39") (pin "1") (pinfunction "P_1") (pintype "passive"))
    )
    (net (code "131") (name "Net-(PAD40-P)") (class "Default")
      (node (ref "E40") (pin "10") (pinfunction "10_10") (pintype "passive"))
      (node (ref "PAD40") (pin "1") (pinfunction "P_1") (pintype "passive"))
    )
    (net (code "132") (name "Net-(PAD41-P)") (class "Default")
      (node (ref "E40") (pin "9") (pinfunction "9_9") (pintype "passive"))
      (node (ref "PAD41") (pin "1") (pinfunction "P_1") (pintype "passive"))
    )
    (net (code "133") (name "Net-(PAD42-P)") (class "Default")
      (node (ref "E39") (pin "1") (pinfunction "1_1") (pintype "passive"))
      (node (ref "PAD42") (pin "1") (pinfunction "P_1") (pintype "passive"))
    )
    (net (code "134") (name "Net-(PAD43-P)") (class "Default")
      (node (ref "E39") (pin "2") (pinfunction "2_2") (pintype "passive"))
      (node (ref "PAD43") (pin "1") (pinfunction "P_1") (pintype "passive"))
    )
    (net (code "135") (name "Net-(PAD44-P)") (class "Default")
      (node (ref "E39") (pin "3") (pinfunction "3_3") (pintype "passive"))
      (node (ref "PAD44") (pin "1") (pinfunction "P_1") (pintype "passive"))
    )
    (net (code "136") (name "Net-(PAD45-P)") (class "Default")
      (node (ref "E39") (pin "4") (pinfunction "4_4") (pintype "passive"))
      (node (ref "PAD45") (pin "1") (pinfunction "P_1") (pintype "passive"))
    )
    (net (code "137") (name "Net-(PAD46-P)") (class "Default")
      (node (ref "E39") (pin "5") (pinfunction "5_5") (pintype "passive"))
      (node (ref "PAD46") (pin "1") (pinfunction "P_1") (pintype "passive"))
    )
    (net (code "138") (name "Net-(PAD47-P)") (class "Default")
      (node (ref "E39") (pin "6") (pinfunction "6_6") (pintype "passive"))
      (node (ref "PAD47") (pin "1") (pinfunction "P_1") (pintype "passive"))
    )
    (net (code "139") (name "Net-(PAD48-P)") (class "Default")
      (node (ref "E39") (pin "7") (pinfunction "7_7") (pintype "passive"))
      (node (ref "PAD48") (pin "1") (pinfunction "P_1") (pintype "passive"))
    )
    (net (code "140") (name "Net-(PAD49-P)") (class "Default")
      (node (ref "E39") (pin "8") (pinfunction "8_8") (pintype "passive"))
      (node (ref "PAD49") (pin "1") (pinfunction "P_1") (pintype "passive"))
    )
    (net (code "141") (name "Net-(PAD50-P)") (class "Default")
      (node (ref "E39") (pin "16") (pinfunction "16_16") (pintype "passive"))
      (node (ref "PAD50") (pin "1") (pinfunction "P_1") (pintype "passive"))
    )
    (net (code "142") (name "Net-(PAD51-P)") (class "Default")
      (node (ref "E39") (pin "15") (pinfunction "15_15") (pintype "passive"))
      (node (ref "PAD51") (pin "1") (pinfunction "P_1") (pintype "passive"))
    )
    (net (code "143") (name "Net-(PAD52-P)") (class "Default")
      (node (ref "E39") (pin "14") (pinfunction "14_14") (pintype "passive"))
      (node (ref "PAD52") (pin "1") (pinfunction "P_1") (pintype "passive"))
    )
    (net (code "144") (name "Net-(PAD53-P)") (class "Default")
      (node (ref "E39") (pin "13") (pinfunction "13_13") (pintype "passive"))
      (node (ref "PAD53") (pin "1") (pinfunction "P_1") (pintype "passive"))
    )
    (net (code "145") (name "Net-(PAD54-P)") (class "Default")
      (node (ref "E39") (pin "12") (pinfunction "12_12") (pintype "passive"))
      (node (ref "PAD54") (pin "1") (pinfunction "P_1") (pintype "passive"))
    )
    (net (code "146") (name "Net-(PAD55-P)") (class "Default")
      (node (ref "E39") (pin "11") (pinfunction "11_11") (pintype "passive"))
      (node (ref "PAD55") (pin "1") (pinfunction "P_1") (pintype "passive"))
    )
    (net (code "147") (name "Net-(PAD56-P)") (class "Default")
      (node (ref "E39") (pin "10") (pinfunction "10_10") (pintype "passive"))
      (node (ref "PAD56") (pin "1") (pinfunction "P_1") (pintype "passive"))
    )
    (net (code "148") (name "Net-(PAD57-P)") (class "Default")
      (node (ref "E39") (pin "9") (pinfunction "9_9") (pintype "passive"))
      (node (ref "PAD57") (pin "1") (pinfunction "P_1") (pintype "passive"))
    )
    (net (code "149") (name "PARITY") (class "Default")
      (node (ref "E15") (pin "1") (pinfunction "I0_1") (pintype "input"))
      (node (ref "E15") (pin "13") (pinfunction "I1_13") (pintype "input"))
      (node (ref "E15") (pin "2") (pinfunction "I1_2") (pintype "input"))
      (node (ref "E4") (pin "15") (pinfunction "RCO_15") (pintype "output"))
    )
    (net (code "150") (name "RD") (class "Default")
      (node (ref "E25") (pin "1") (pinfunction "I_1") (pintype "input"))
      (node (ref "E32") (pin "10") (pinfunction "I1_10") (pintype "input"))
      (node (ref "E35") (pin "10") (pinfunction "O_10") (pintype "output"))
    )
    (net (code "151") (name "RUN") (class "Default")
      (node (ref "E18") (pin "11") (pinfunction "I0_11") (pintype "input"))
      (node (ref "E30") (pin "9") (pinfunction "Q_9") (pintype "output"))
      (node (ref "IC9") (pin "6") (pinfunction "I0_6") (pintype "input"))
      (node (ref "IC9") (pin "7") (pinfunction "I1_7") (pintype "input"))
    )
    (net (code "152") (name "RX_DATA") (class "Default")
      (node (ref "E22") (pin "2") (pinfunction "J_2") (pintype "input"))
      (node (ref "E22") (pin "3") (pinfunction "K_3") (pintype "input"))
      (node (ref "E35") (pin "1") (pinfunction "O_1") (pintype "output"))
    )
    (net (code "153") (name "SHIFT") (class "Default")
      (node (ref "E32") (pin "3") (pinfunction "I0_3") (pintype "input"))
      (node (ref "E35") (pin "4") (pinfunction "O_4") (pintype "output"))
    )
    (net (code "154") (name "TR_SKIP") (class "Default")
      (node (ref "E18") (pin "1") (pinfunction "O_1") (pintype "output"))
      (node (ref "E19") (pin "16") (pinfunction "K_16") (pintype "input"))
      (node (ref "E20") (pin "1") (pinfunction "I0_1") (pintype "input"))
      (node (ref "E26") (pin "2") (pinfunction "I1_2") (pintype "input"))
    )
    (net (code "155") (name "VCC") (class "Default")
      (node (ref "C1") (pin "1") (pinfunction "1_1") (pintype "passive"))
      (node (ref "C10") (pin "1") (pinfunction "1_1") (pintype "passive"))
      (node (ref "C11") (pin "1") (pinfunction "1_1") (pintype "passive"))
      (node (ref "C12") (pin "1") (pinfunction "1_1") (pintype "passive"))
      (node (ref "C13") (pin "1") (pinfunction "1_1") (pintype "passive"))
      (node (ref "C14") (pin "1") (pinfunction "1_1") (pintype "passive"))
      (node (ref "C15") (pin "1") (pinfunction "1_1") (pintype "passive"))
      (node (ref "C16") (pin "1") (pinfunction "1_1") (pintype "passive"))
      (node (ref "C17") (pin "1") (pinfunction "1_1") (pintype "passive"))
      (node (ref "C18") (pin "1") (pinfunction "1_1") (pintype "passive"))
      (node (ref "C19") (pin "1") (pinfunction "1_1") (pintype "passive"))
      (node (ref "C2") (pin "1") (pinfunction "1_1") (pintype "passive"))
      (node (ref "C20") (pin "1") (pinfunction "1_1") (pintype "passive"))
      (node (ref "C21") (pin "1") (pinfunction "1_1") (pintype "passive"))
      (node (ref "C22") (pin "1") (pinfunction "1_1") (pintype "passive"))
      (node (ref "C23") (pin "1") (pinfunction "1_1") (pintype "passive"))
      (node (ref "C24") (pin "1") (pinfunction "1_1") (pintype "passive"))
      (node (ref "C25") (pin "1") (pinfunction "1_1") (pintype "passive"))
      (node (ref "C26") (pin "1") (pinfunction "1_1") (pintype "passive"))
      (node (ref "C27") (pin "1") (pinfunction "1_1") (pintype "passive"))
      (node (ref "C28") (pin "1") (pinfunction "1_1") (pintype "passive"))
      (node (ref "C29") (pin "1") (pinfunction "1_1") (pintype "passive"))
      (node (ref "C3") (pin "1") (pinfunction "1_1") (pintype "passive"))
      (node (ref "C30") (pin "1") (pinfunction "1_1") (pintype "passive"))
      (node (ref "C31") (pin "1") (pinfunction "1_1") (pintype "passive"))
      (node (ref "C32") (pin "1") (pinfunction "1_1") (pintype "passive"))
      (node (ref "C33") (pin "1") (pinfunction "1_1") (pintype "passive"))
      (node (ref "C34") (pin "1") (pinfunction "1_1") (pintype "passive"))
      (node (ref "C35") (pin "1") (pinfunction "1_1") (pintype "passive"))
      (node (ref "C36") (pin "1") (pinfunction "1_1") (pintype "passive"))
      (node (ref "C37") (pin "1") (pinfunction "1_1") (pintype "passive"))
      (node (ref "C38") (pin "1") (pinfunction "1_1") (pintype "passive"))
      (node (ref "C39") (pin "1") (pinfunction "1_1") (pintype "passive"))
      (node (ref "C4") (pin "1") (pinfunction "1_1") (pintype "passive"))
      (node (ref "C40") (pin "+") (pinfunction "+_+") (pintype "passive"))
      (node (ref "C5") (pin "1") (pinfunction "1_1") (pintype "passive"))
      (node (ref "C6") (pin "1") (pinfunction "1_1") (pintype "passive"))
      (node (ref "C7") (pin "1") (pinfunction "1_1") (pintype "passive"))
      (node (ref "C8") (pin "1") (pinfunction "1_1") (pintype "passive"))
      (node (ref "C9") (pin "1") (pinfunction "1_1") (pintype "passive"))
      (node (ref "E14") (pin "6") (pinfunction "G1_6") (pintype "input"))
      (node (ref "E16") (pin "10") (pinfunction "PRE_10") (pintype "input"))
      (node (ref "E16") (pin "4") (pinfunction "PRE_4") (pintype "input"))
      (node (ref "E17") (pin "7") (pinfunction "PRE_7") (pintype "input"))
      (node (ref "E2") (pin "1") (pinfunction "CLR_1") (pintype "input"))
      (node (ref "E2") (pin "10") (pinfunction "PRE_10") (pintype "input"))
      (node (ref "E2") (pin "11") (pinfunction "CLK_11") (pintype "input"))
      (node (ref "E2") (pin "12") (pinfunction "D_12") (pintype "input"))
      (node (ref "E2") (pin "13") (pinfunction "CLR_13") (pintype "input"))
      (node (ref "E20") (pin "10") (pinfunction "I1_10") (pintype "input"))
      (node (ref "E20") (pin "9") (pinfunction "I0_9") (pintype "input"))
      (node (ref "E25") (pin "11") (pinfunction "I_11") (pintype "input"))
      (node (ref "E25") (pin "13") (pinfunction "I_13") (pintype "input"))
      (node (ref "E30") (pin "10") (pinfunction "PRE_10") (pintype "input"))
      (node (ref "E30") (pin "12") (pinfunction "D_12") (pintype "input"))
      (node (ref "E30") (pin "4") (pinfunction "PRE_4") (pintype "input"))
      (node (ref "R1") (pin "2") (pinfunction "2_2") (pintype "passive"))
      (node (ref "R18") (pin "2") (pinfunction "2_2") (pintype "passive"))
      (node (ref "R19") (pin "1") (pinfunction "1_1") (pintype "passive"))
      (node (ref "R2") (pin "2") (pinfunction "2_2") (pintype "passive"))
      (node (ref "R3") (pin "2") (pinfunction "2_2") (pintype "passive"))
      (node (ref "R4") (pin "2") (pinfunction "2_2") (pintype "passive"))
      (node (ref "R5") (pin "2") (pinfunction "2_2") (pintype "passive"))
      (node (ref "R6") (pin "2") (pinfunction "2_2") (pintype "passive"))
      (node (ref "R7") (pin "2") (pinfunction "2_2") (pintype "passive"))
      (node (ref "R8") (pin "2") (pinfunction "2_2") (pintype "passive"))
      (node (ref "R9") (pin "2") (pinfunction "2_2") (pintype "passive"))
      (node (ref "VCC") (pin "1") (pinfunction "P_1") (pintype "passive"))
    )
    (net (code "156") (name "WRT") (class "Default")
      (node (ref "E10") (pin "5") (pinfunction "I2_5") (pintype "input"))
      (node (ref "E15") (pin "10") (pinfunction "I1_10") (pintype "input"))
      (node (ref "E25") (pin "2") (pinfunction "O_2") (pintype "output"))
      (node (ref "IC7") (pin "6") (pinfunction "I0_6") (pintype "input"))
    )
    (net (code "157") (name "XDR2") (class "Default")
      (node (ref "E10") (pin "2") (pinfunction "I1_2") (pintype "input"))
      (node (ref "E5") (pin "12") (pinfunction "I0_12") (pintype "input"))
      (node (ref "E5") (pin "8") (pinfunction "O_8") (pintype "output"))
    )
    (net (code "158") (name "XFER_REQ") (class "Default")
      (node (ref "E19") (pin "4") (pinfunction "J_4") (pintype "input"))
      (node (ref "E20") (pin "12") (pinfunction "I0_12") (pintype "input"))
      (node (ref "E26") (pin "1") (pinfunction "I0_1") (pintype "input"))
      (node (ref "E36") (pin "4") (pinfunction "O_4") (pintype "output"))
    )
    (net (code "159") (name "unconnected-(D34L1-2-PadB)") (class "Default")
      (node (ref "D34L1") (pin "B") (pinfunction "2_B") (pintype "bidirectional"))
    )
    (net (code "160") (name "unconnected-(D34L1-34-PadNN)") (class "Default")
      (node (ref "D34L1") (pin "NN") (pinfunction "34_NN") (pintype "bidirectional"))
    )
    (net (code "161") (name "unconnected-(D34L1-38-PadTT)") (class "Default")
      (node (ref "D34L1") (pin "TT") (pinfunction "38_TT") (pintype "bidirectional"))
    )
    (net (code "162") (name "unconnected-(D34L1-40-PadVV)") (class "Default")
      (node (ref "D34L1") (pin "VV") (pinfunction "40_VV") (pintype "bidirectional"))
    )
    (net (code "163") (name "unconnected-(D34L2-2-PadB)") (class "Default")
      (node (ref "D34L2") (pin "B") (pinfunction "2_B") (pintype "bidirectional"))
    )
    (net (code "164") (name "unconnected-(D34L2-34-PadNN)") (class "Default")
      (node (ref "D34L2") (pin "NN") (pinfunction "34_NN") (pintype "bidirectional"))
    )
    (net (code "165") (name "unconnected-(D34L2-38-PadTT)") (class "Default")
      (node (ref "D34L2") (pin "TT") (pinfunction "38_TT") (pintype "bidirectional"))
    )
    (net (code "166") (name "unconnected-(D34L2-40-PadVV)") (class "Default")
      (node (ref "D34L2") (pin "VV") (pinfunction "40_VV") (pintype "bidirectional"))
    )
    (net (code "167") (name "unconnected-(D35L1-2-PadB)") (class "Default")
      (node (ref "D35L1") (pin "B") (pinfunction "2_B") (pintype "bidirectional"))
    )
    (net (code "168") (name "unconnected-(D35L1-40-PadVV)") (class "Default")
      (node (ref "D35L1") (pin "VV") (pinfunction "40_VV") (pintype "bidirectional"))
    )
    (net (code "169") (name "unconnected-(D35L2-2-PadB)") (class "Default")
      (node (ref "D35L2") (pin "B") (pinfunction "2_B") (pintype "bidirectional"))
    )
    (net (code "170") (name "unconnected-(D35L2-40-PadVV)") (class "Default")
      (node (ref "D35L2") (pin "VV") (pinfunction "40_VV") (pintype "bidirectional"))
    )
    (net (code "171") (name "unconnected-(D36L1-2-PadB)") (class "Default")
      (node (ref "D36L1") (pin "B") (pinfunction "2_B") (pintype "bidirectional"))
    )
    (net (code "172") (name "unconnected-(D36L1-40-PadVV)") (class "Default")
      (node (ref "D36L1") (pin "VV") (pinfunction "40_VV") (pintype "bidirectional"))
    )
    (net (code "173") (name "unconnected-(D36L2-2-PadB)") (class "Default")
      (node (ref "D36L2") (pin "B") (pinfunction "2_B") (pintype "bidirectional"))
    )
    (net (code "174") (name "unconnected-(D36L2-40-PadVV)") (class "Default")
      (node (ref "D36L2") (pin "VV") (pinfunction "40_VV") (pintype "bidirectional"))
    )
    (net (code "175") (name "unconnected-(E2A-Q-Pad5)") (class "Default")
      (node (ref "E2") (pin "5") (pinfunction "Q_5") (pintype "output"))
    )
    (net (code "176") (name "unconnected-(E2B-Q-Pad9)") (class "Default")
      (node (ref "E2") (pin "9") (pinfunction "Q_9") (pintype "output"))
    )
    (net (code "177") (name "unconnected-(E2B-~{Q}-Pad8)") (class "Default")
      (node (ref "E2") (pin "8") (pinfunction "~{Q}_8") (pintype "output"))
    )
    (net (code "178") (name "unconnected-(E4A-QA-Pad14)") (class "Default")
      (node (ref "E4") (pin "14") (pinfunction "QA_14") (pintype "output"))
    )
    (net (code "179") (name "unconnected-(E4A-QB-Pad13)") (class "Default")
      (node (ref "E4") (pin "13") (pinfunction "QB_13") (pintype "output"))
    )
    (net (code "180") (name "unconnected-(E4A-QC-Pad12)") (class "Default")
      (node (ref "E4") (pin "12") (pinfunction "QC_12") (pintype "output"))
    )
    (net (code "181") (name "unconnected-(E4A-QD-Pad11)") (class "Default")
      (node (ref "E4") (pin "11") (pinfunction "QD_11") (pintype "output"))
    )
    (net (code "182") (name "unconnected-(E11A-Y0-Pad15)") (class "Default")
      (node (ref "E11") (pin "15") (pinfunction "Y0_15") (pintype "output"))
    )
    (net (code "183") (name "unconnected-(E11A-Y2-Pad13)") (class "Default")
      (node (ref "E11") (pin "13") (pinfunction "Y2_13") (pintype "output"))
    )
    (net (code "184") (name "unconnected-(E11A-Y3-Pad12)") (class "Default")
      (node (ref "E11") (pin "12") (pinfunction "Y3_12") (pintype "output"))
    )
    (net (code "185") (name "unconnected-(E11A-Y4-Pad11)") (class "Default")
      (node (ref "E11") (pin "11") (pinfunction "Y4_11") (pintype "output"))
    )
    (net (code "186") (name "unconnected-(E11A-Y5-Pad10)") (class "Default")
      (node (ref "E11") (pin "10") (pinfunction "Y5_10") (pintype "output"))
    )
    (net (code "187") (name "unconnected-(E11A-Y6-Pad9)") (class "Default")
      (node (ref "E11") (pin "9") (pinfunction "Y6_9") (pintype "output"))
    )
    (net (code "188") (name "unconnected-(E12A-Y0-Pad15)") (class "Default")
      (node (ref "E12") (pin "15") (pinfunction "Y0_15") (pintype "output"))
    )
    (net (code "189") (name "unconnected-(E12A-Y1-Pad14)") (class "Default")
      (node (ref "E12") (pin "14") (pinfunction "Y1_14") (pintype "output"))
    )
    (net (code "190") (name "unconnected-(E12A-Y4-Pad11)") (class "Default")
      (node (ref "E12") (pin "11") (pinfunction "Y4_11") (pintype "output"))
    )
    (net (code "191") (name "unconnected-(E12A-Y5-Pad10)") (class "Default")
      (node (ref "E12") (pin "10") (pinfunction "Y5_10") (pintype "output"))
    )
    (net (code "192") (name "unconnected-(E12A-Y6-Pad9)") (class "Default")
      (node (ref "E12") (pin "9") (pinfunction "Y6_9") (pintype "output"))
    )
    (net (code "193") (name "unconnected-(E12A-Y7-Pad7)") (class "Default")
      (node (ref "E12") (pin "7") (pinfunction "Y7_7") (pintype "output"))
    )
    (net (code "194") (name "unconnected-(E13A-Y0-Pad15)") (class "Default")
      (node (ref "E13") (pin "15") (pinfunction "Y0_15") (pintype "output"))
    )
    (net (code "195") (name "unconnected-(E13A-Y1-Pad14)") (class "Default")
      (node (ref "E13") (pin "14") (pinfunction "Y1_14") (pintype "output"))
    )
    (net (code "196") (name "unconnected-(E13A-Y2-Pad13)") (class "Default")
      (node (ref "E13") (pin "13") (pinfunction "Y2_13") (pintype "output"))
    )
    (net (code "197") (name "unconnected-(E13A-Y3-Pad12)") (class "Default")
      (node (ref "E13") (pin "12") (pinfunction "Y3_12") (pintype "output"))
    )
    (net (code "198") (name "unconnected-(E17B-Q-Pad11)") (class "Default")
      (node (ref "E17") (pin "11") (pinfunction "Q_11") (pintype "output"))
    )
    (net (code "199") (name "unconnected-(E19A-Q-Pad15)") (class "Default")
      (node (ref "E19") (pin "15") (pinfunction "Q_15") (pintype "output"))
    )
    (net (code "200") (name "unconnected-(E19B-Q-Pad11)") (class "Default")
      (node (ref "E19") (pin "11") (pinfunction "Q_11") (pintype "output"))
    )
    (net (code "201") (name "unconnected-(E20C-O-Pad8)") (class "Default")
      (node (ref "E20") (pin "8") (pinfunction "O_8") (pintype "output"))
    )
    (net (code "202") (name "unconnected-(E21A-~{QD}-Pad11)") (class "Default")
      (node (ref "E21") (pin "11") (pinfunction "~{QD}_11") (pintype "output"))
    )
    (net (code "203") (name "unconnected-(E22A-~{QD}-Pad11)") (class "Default")
      (node (ref "E22") (pin "11") (pinfunction "~{QD}_11") (pintype "output"))
    )
    (net (code "204") (name "unconnected-(E23A-~{QD}-Pad11)") (class "Default")
      (node (ref "E23") (pin "11") (pinfunction "~{QD}_11") (pintype "output"))
    )
    (net (code "205") (name "unconnected-(E26D-O-Pad11)") (class "Default")
      (node (ref "E26") (pin "11") (pinfunction "O_11") (pintype "output"))
    )
    (net (code "206") (name "unconnected-(E30A-~{Q}-Pad6)") (class "Default")
      (node (ref "E30") (pin "6") (pinfunction "~{Q}_6") (pintype "output"))
    )
    (net (code "207") (name "unconnected-(E30B-~{Q}-Pad8)") (class "Default")
      (node (ref "E30") (pin "8") (pinfunction "~{Q}_8") (pintype "output"))
    )
    (net (code "208") (name "unconnected-(E36D-O-Pad13)") (class "Default")
      (node (ref "E36") (pin "13") (pinfunction "O_13") (pintype "output"))
    )
    (net (code "209") (name "unconnected-(LASTDEV-Pad8)") (class "Default")
      (node (ref "LASTDEV") (pin "8") (pinfunction "8_8") (pintype "passive"))
    )
    (net (code "210") (name "unconnected-(LASTDEV-Pad9)") (class "Default")
      (node (ref "LASTDEV") (pin "9") (pinfunction "9_9") (pintype "passive"))
    )
    (net (code "211") (name "unconnected-(LASTDEV-Pad10)") (class "Default")
      (node (ref "LASTDEV") (pin "10") (pinfunction "10_10") (pintype "passive"))
    )
    (net (code "212") (name "~{ACB00}") (class "Default")
      (node (ref "D34L1") (pin "D") (pinfunction "4_D") (pintype "bidirectional"))
      (node (ref "D34L2") (pin "D") (pinfunction "4_D") (pintype "bidirectional"))
      (node (ref "IC6") (pin "3") (pinfunction "O_3") (pintype "open_collector"))
    )
    (net (code "213") (name "~{ACB01}") (class "Default")
      (node (ref "D34L1") (pin "J") (pinfunction "8_J") (pintype "bidirectional"))
      (node (ref "D34L2") (pin "J") (pinfunction "8_J") (pintype "bidirectional"))
      (node (ref "IC6") (pin "5") (pinfunction "O_5") (pintype "open_collector"))
    )
    (net (code "214") (name "~{ACB02}") (class "Default")
      (node (ref "D34L1") (pin "N") (pinfunction "12_N") (pintype "bidirectional"))
      (node (ref "D34L2") (pin "N") (pinfunction "12_N") (pintype "bidirectional"))
      (node (ref "IC1") (pin "3") (pinfunction "O_3") (pintype "open_collector"))
    )
    (net (code "215") (name "~{ACB03}") (class "Default")
      (node (ref "D34L1") (pin "T") (pinfunction "16_T") (pintype "bidirectional"))
      (node (ref "D34L2") (pin "T") (pinfunction "16_T") (pintype "bidirectional"))
      (node (ref "IC2") (pin "5") (pinfunction "O_5") (pintype "open_collector"))
    )
    (net (code "216") (name "~{ACB04}") (class "Default")
      (node (ref "D34L1") (pin "X") (pinfunction "20_X") (pintype "bidirectional"))
      (node (ref "D34L2") (pin "X") (pinfunction "20_X") (pintype "bidirectional"))
      (node (ref "IC1") (pin "5") (pinfunction "O_5") (pintype "open_collector"))
    )
    (net (code "217") (name "~{ACB05}") (class "Default")
      (node (ref "D34L1") (pin "BB") (pinfunction "24_BB") (pintype "bidirectional"))
      (node (ref "D34L2") (pin "BB") (pinfunction "24_BB") (pintype "bidirectional"))
      (node (ref "IC4") (pin "3") (pinfunction "O_3") (pintype "open_collector"))
    )
    (net (code "218") (name "~{ACB06}") (class "Default")
      (node (ref "D34L1") (pin "FF") (pinfunction "28_FF") (pintype "bidirectional"))
      (node (ref "D34L2") (pin "FF") (pinfunction "28_FF") (pintype "bidirectional"))
      (node (ref "IC3") (pin "3") (pinfunction "O_3") (pintype "open_collector"))
    )
    (net (code "219") (name "~{ACB07}") (class "Default")
      (node (ref "D34L1") (pin "LL") (pinfunction "32_LL") (pintype "bidirectional"))
      (node (ref "D34L2") (pin "LL") (pinfunction "32_LL") (pintype "bidirectional"))
      (node (ref "IC3") (pin "5") (pinfunction "O_5") (pintype "open_collector"))
    )
    (net (code "220") (name "~{ACB08}") (class "Default")
      (node (ref "D34L1") (pin "RR") (pinfunction "36_RR") (pintype "bidirectional"))
      (node (ref "D34L2") (pin "RR") (pinfunction "36_RR") (pintype "bidirectional"))
      (node (ref "IC4") (pin "5") (pinfunction "O_5") (pintype "open_collector"))
    )
    (net (code "221") (name "~{ACB09}") (class "Default")
      (node (ref "D34L1") (pin "F") (pinfunction "6_F") (pintype "bidirectional"))
      (node (ref "D34L2") (pin "F") (pinfunction "6_F") (pintype "bidirectional"))
      (node (ref "IC5") (pin "3") (pinfunction "O_3") (pintype "open_collector"))
    )
    (net (code "222") (name "~{ACB10}") (class "Default")
      (node (ref "D34L1") (pin "L") (pinfunction "10_L") (pintype "bidirectional"))
      (node (ref "D34L2") (pin "L") (pinfunction "10_L") (pintype "bidirectional"))
      (node (ref "IC5") (pin "5") (pinfunction "O_5") (pintype "open_collector"))
    )
    (net (code "223") (name "~{ACB11}") (class "Default")
      (node (ref "D34L1") (pin "R") (pinfunction "14_R") (pintype "bidirectional"))
      (node (ref "D34L2") (pin "R") (pinfunction "14_R") (pintype "bidirectional"))
      (node (ref "IC2") (pin "3") (pinfunction "O_3") (pintype "open_collector"))
    )
    (net (code "224") (name "~{ACCLEAR}") (class "Default")
      (node (ref "D34L1") (pin "DD") (pinfunction "26_DD") (pintype "bidirectional"))
      (node (ref "D34L2") (pin "DD") (pinfunction "26_DD") (pintype "bidirectional"))
      (node (ref "IC7") (pin "3") (pinfunction "O_3") (pintype "open_collector"))
    )
    (net (code "225") (name "~{BMB03}") (class "Default")
      (node (ref "D35L1") (pin "T") (pinfunction "16_T") (pintype "bidirectional"))
      (node (ref "D35L2") (pin "T") (pinfunction "16_T") (pintype "bidirectional"))
    )
    (net (code "226") (name "~{BMB04}") (class "Default")
      (node (ref "D35L1") (pin "BB") (pinfunction "24_BB") (pintype "bidirectional"))
      (node (ref "D35L2") (pin "BB") (pinfunction "24_BB") (pintype "bidirectional"))
    )
    (net (code "227") (name "~{BMB05}") (class "Default")
      (node (ref "D35L1") (pin "LL") (pinfunction "32_LL") (pintype "bidirectional"))
      (node (ref "D35L2") (pin "LL") (pinfunction "32_LL") (pintype "bidirectional"))
    )
    (net (code "228") (name "~{BMB06}") (class "Default")
      (node (ref "D35L1") (pin "F") (pinfunction "6_F") (pintype "bidirectional"))
      (node (ref "D35L2") (pin "F") (pinfunction "6_F") (pintype "bidirectional"))
    )
    (net (code "229") (name "~{BMB07}") (class "Default")
      (node (ref "D35L1") (pin "R") (pinfunction "14_R") (pintype "bidirectional"))
      (node (ref "D35L2") (pin "R") (pinfunction "14_R") (pintype "bidirectional"))
    )
    (net (code "230") (name "~{BMB08}") (class "Default")
      (node (ref "D35L1") (pin "Z") (pinfunction "22_Z") (pintype "bidirectional"))
      (node (ref "D35L2") (pin "Z") (pinfunction "22_Z") (pintype "bidirectional"))
    )
    (net (code "231") (name "~{BRUN}") (class "Default")
      (node (ref "D34L1") (pin "JJ") (pinfunction "30_JJ") (pintype "bidirectional"))
      (node (ref "D34L2") (pin "JJ") (pinfunction "30_JJ") (pintype "bidirectional"))
    )
    (net (code "232") (name "~{CLK_PARITY}") (class "Default")
      (node (ref "E17") (pin "6") (pinfunction "CLK_6") (pintype "input"))
      (node (ref "E32") (pin "6") (pinfunction "O_6") (pintype "output"))
      (node (ref "E5") (pin "4") (pinfunction "I0_4") (pintype "input"))
      (node (ref "E5") (pin "5") (pinfunction "I1_5") (pintype "input"))
    )
    (net (code "233") (name "~{DONE}") (class "Default")
      (node (ref "E10") (pin "4") (pinfunction "I1_4") (pintype "input"))
      (node (ref "E25") (pin "4") (pinfunction "O_4") (pintype "output"))
      (node (ref "E31") (pin "12") (pinfunction "I2_12") (pintype "input"))
    )
    (net (code "234") (name "~{ENB_BUF_LD}") (class "Default")
      (node (ref "E21") (pin "9") (pinfunction "S/~{L}_9") (pintype "input"))
      (node (ref "E22") (pin "9") (pinfunction "S/~{L}_9") (pintype "input"))
      (node (ref "E23") (pin "9") (pinfunction "S/~{L}_9") (pintype "input"))
      (node (ref "E24") (pin "11") (pinfunction "O_11") (pintype "output"))
      (node (ref "E32") (pin "13") (pinfunction "I2_13") (pintype "input"))
      (node (ref "E32") (pin "2") (pinfunction "I1_2") (pintype "input"))
      (node (ref "E4") (pin "9") (pinfunction "LD_9") (pintype "input"))
    )
    (net (code "235") (name "~{INIT1}") (class "Default")
      (node (ref "E11") (pin "7") (pinfunction "Y7_7") (pintype "output"))
      (node (ref "E2") (pin "4") (pinfunction "PRE_4") (pintype "input"))
    )
    (net (code "236") (name "~{INIT4}") (class "Default")
      (node (ref "E13") (pin "7") (pinfunction "Y7_7") (pintype "output"))
      (node (ref "E2") (pin "3") (pinfunction "CLK_3") (pintype "input"))
    )
    (net (code "237") (name "~{INIT}") (class "Default")
      (node (ref "E15") (pin "6") (pinfunction "O_6") (pintype "output"))
      (node (ref "E16") (pin "1") (pinfunction "CLR_1") (pintype "input"))
      (node (ref "E16") (pin "13") (pinfunction "CLR_13") (pintype "input"))
      (node (ref "E17") (pin "3") (pinfunction "CLR_3") (pintype "input"))
      (node (ref "E19") (pin "3") (pinfunction "CLR_3") (pintype "input"))
      (node (ref "E19") (pin "8") (pinfunction "CLR_8") (pintype "input"))
      (node (ref "E21") (pin "1") (pinfunction "CLR_1") (pintype "input"))
      (node (ref "E22") (pin "1") (pinfunction "CLR_1") (pintype "input"))
      (node (ref "E23") (pin "1") (pinfunction "CLR_1") (pintype "input"))
      (node (ref "E24") (pin "9") (pinfunction "I0_9") (pintype "input"))
      (node (ref "E30") (pin "1") (pinfunction "CLR_1") (pintype "input"))
      (node (ref "E4") (pin "1") (pinfunction "CLR_1") (pintype "input"))
    )
    (net (code "238") (name "~{INTR4}") (class "Default")
      (node (ref "E13") (pin "9") (pinfunction "Y6_9") (pintype "output"))
      (node (ref "E30") (pin "3") (pinfunction "CLK_3") (pintype "input"))
    )
    (net (code "239") (name "~{INT_RQ}") (class "Default")
      (node (ref "D34L1") (pin "Z") (pinfunction "22_Z") (pintype "bidirectional"))
      (node (ref "D34L2") (pin "Z") (pinfunction "22_Z") (pintype "bidirectional"))
      (node (ref "IC10") (pin "5") (pinfunction "O_5") (pintype "open_collector"))
    )
    (net (code "240") (name "~{IOS}") (class "Default")
      (node (ref "D34L1") (pin "V") (pinfunction "18_V") (pintype "bidirectional"))
      (node (ref "D34L2") (pin "V") (pinfunction "18_V") (pintype "bidirectional"))
      (node (ref "IC10") (pin "3") (pinfunction "O_3") (pintype "open_collector"))
    )
    (net (code "241") (name "~{LCD1}") (class "Default")
      (node (ref "E10") (pin "9") (pinfunction "I0_9") (pintype "input"))
      (node (ref "E11") (pin "14") (pinfunction "Y1_14") (pintype "output"))
      (node (ref "E16") (pin "11") (pinfunction "CLK_11") (pintype "input"))
      (node (ref "E16") (pin "3") (pinfunction "CLK_3") (pintype "input"))
      (node (ref "E24") (pin "5") (pinfunction "I1_5") (pintype "input"))
      (node (ref "E25") (pin "5") (pinfunction "I_5") (pintype "input"))
    )
    (net (code "242") (name "~{MAINT}") (class "Default")
      (node (ref "E10") (pin "3") (pinfunction "I0_3") (pintype "input"))
      (node (ref "E16") (pin "8") (pinfunction "~{Q}_8") (pintype "output"))
      (node (ref "E17") (pin "2") (pinfunction "PRE_2") (pintype "input"))
      (node (ref "E19") (pin "2") (pinfunction "PRE_2") (pintype "input"))
      (node (ref "E19") (pin "7") (pinfunction "PRE_7") (pintype "input"))
      (node (ref "E24") (pin "13") (pinfunction "I1_13") (pintype "input"))
      (node (ref "E31") (pin "5") (pinfunction "I3_5") (pintype "input"))
      (node (ref "E31") (pin "9") (pinfunction "I0_9") (pintype "input"))
    )
    (net (code "243") (name "~{MYDEV}") (class "Default")
      (node (ref "E11") (pin "4") (pinfunction "G2A_4") (pintype "input"))
      (node (ref "E12") (pin "4") (pinfunction "G2A_4") (pintype "input"))
      (node (ref "E13") (pin "4") (pinfunction "G2A_4") (pintype "input"))
      (node (ref "IOT") (pin "1") (pinfunction "P_1") (pintype "passive"))
    )
    (net (code "244") (name "~{PARITY}") (class "Default")
      (node (ref "E15") (pin "12") (pinfunction "I0_12") (pintype "input"))
      (node (ref "E17") (pin "10") (pinfunction "~{Q}_10") (pintype "output"))
    )
    (net (code "245") (name "~{RX_12_BIT}") (class "Default")
      (node (ref "DRIVE") (pin "FF") (pinfunction "28_FF") (pintype "bidirectional"))
      (node (ref "IC8") (pin "3") (pinfunction "O_3") (pintype "open_collector"))
      (node (ref "R16") (pin "2") (pinfunction "2_2") (pintype "passive"))
      (node (ref "R7") (pin "1") (pinfunction "1_1") (pintype "passive"))
    )
    (net (code "246") (name "~{RX_DATA}") (class "Default")
      (node (ref "DRIVE") (pin "BB") (pinfunction "24_BB") (pintype "bidirectional"))
      (node (ref "E35") (pin "2") (pinfunction "I0_2") (pintype "input"))
      (node (ref "IC7") (pin "5") (pinfunction "O_5") (pintype "open_collector"))
      (node (ref "R17") (pin "2") (pinfunction "2_2") (pintype "passive"))
      (node (ref "R8") (pin "1") (pinfunction "1_1") (pintype "passive"))
    )
    (net (code "247") (name "~{RX_DONE}") (class "Default")
      (node (ref "DRIVE") (pin "X") (pinfunction "20_X") (pintype "bidirectional"))
      (node (ref "E36") (pin "8") (pinfunction "I0_8") (pintype "input"))
      (node (ref "R13") (pin "2") (pinfunction "2_2") (pintype "passive"))
      (node (ref "R4") (pin "1") (pinfunction "1_1") (pintype "passive"))
    )
    (net (code "248") (name "~{RX_ERROR}") (class "Default")
      (node (ref "DRIVE") (pin "J") (pinfunction "8_J") (pintype "bidirectional"))
      (node (ref "E36") (pin "3") (pinfunction "I1_3") (pintype "input"))
      (node (ref "R14") (pin "2") (pinfunction "2_2") (pintype "passive"))
      (node (ref "R5") (pin "1") (pinfunction "1_1") (pintype "passive"))
    )
    (net (code "249") (name "~{RX_INIT}") (class "Default")
      (node (ref "DRIVE") (pin "N") (pinfunction "12_N") (pintype "bidirectional"))
      (node (ref "IC8") (pin "5") (pinfunction "O_5") (pintype "open_collector"))
      (node (ref "R9") (pin "1") (pinfunction "1_1") (pintype "passive"))
    )
    (net (code "250") (name "~{RX_OUT}") (class "Default")
      (node (ref "DRIVE") (pin "RR") (pinfunction "36_RR") (pintype "bidirectional"))
      (node (ref "E35") (pin "8") (pinfunction "I0_8") (pintype "input"))
      (node (ref "R12") (pin "2") (pinfunction "2_2") (pintype "passive"))
      (node (ref "R3") (pin "1") (pinfunction "1_1") (pintype "passive"))
    )
    (net (code "251") (name "~{RX_RUN}") (class "Default")
      (node (ref "DRIVE") (pin "D") (pinfunction "4_D") (pintype "bidirectional"))
      (node (ref "IC9") (pin "5") (pinfunction "O_5") (pintype "open_collector"))
      (node (ref "R15") (pin "2") (pinfunction "2_2") (pintype "passive"))
      (node (ref "R6") (pin "1") (pinfunction "1_1") (pintype "passive"))
    )
    (net (code "252") (name "~{RX_SHIFT}") (class "Default")
      (node (ref "DRIVE") (pin "LL") (pinfunction "32_LL") (pintype "bidirectional"))
      (node (ref "E35") (pin "5") (pinfunction "I0_5") (pintype "input"))
      (node (ref "R10") (pin "2") (pinfunction "2_2") (pintype "passive"))
      (node (ref "R2") (pin "1") (pinfunction "1_1") (pintype "passive"))
    )
    (net (code "253") (name "~{RX_TR_REQ}") (class "Default")
      (node (ref "DRIVE") (pin "T") (pinfunction "16_T") (pintype "bidirectional"))
      (node (ref "E36") (pin "5") (pinfunction "I0_5") (pintype "input"))
      (node (ref "R1") (pin "1") (pinfunction "1_1") (pintype "passive"))
      (node (ref "R11") (pin "2") (pinfunction "2_2") (pintype "passive"))
    )
    (net (code "254") (name "~{SDN4}") (class "Default")
      (node (ref "E13") (pin "10") (pinfunction "Y5_10") (pintype "output"))
      (node (ref "E18") (pin "8") (pinfunction "I0_8") (pintype "input"))
    )
    (net (code "255") (name "~{SER4}") (class "Default")
      (node (ref "E13") (pin "11") (pinfunction "Y4_11") (pintype "output"))
      (node (ref "E18") (pin "5") (pinfunction "I0_5") (pintype "input"))
    )
    (net (code "256") (name "~{STR2}") (class "Default")
      (node (ref "E12") (pin "12") (pinfunction "Y3_12") (pintype "output"))
      (node (ref "E18") (pin "2") (pinfunction "I0_2") (pintype "input"))
    )
    (net (code "257") (name "~{XDR2}") (class "Default")
      (node (ref "E12") (pin "13") (pinfunction "Y2_13") (pintype "output"))
      (node (ref "E24") (pin "4") (pinfunction "I0_4") (pintype "input"))
      (node (ref "E25") (pin "9") (pinfunction "I_9") (pintype "input"))
      (node (ref "E35") (pin "12") (pinfunction "I1_12") (pintype "input"))
      (node (ref "E5") (pin "10") (pinfunction "I1_10") (pintype "input"))
      (node (ref "E5") (pin "9") (pinfunction "I0_9") (pintype "input"))
    )
  )
)
